# reg-board-1.net
KiCad netlist of a schematic drawn in EAGLE
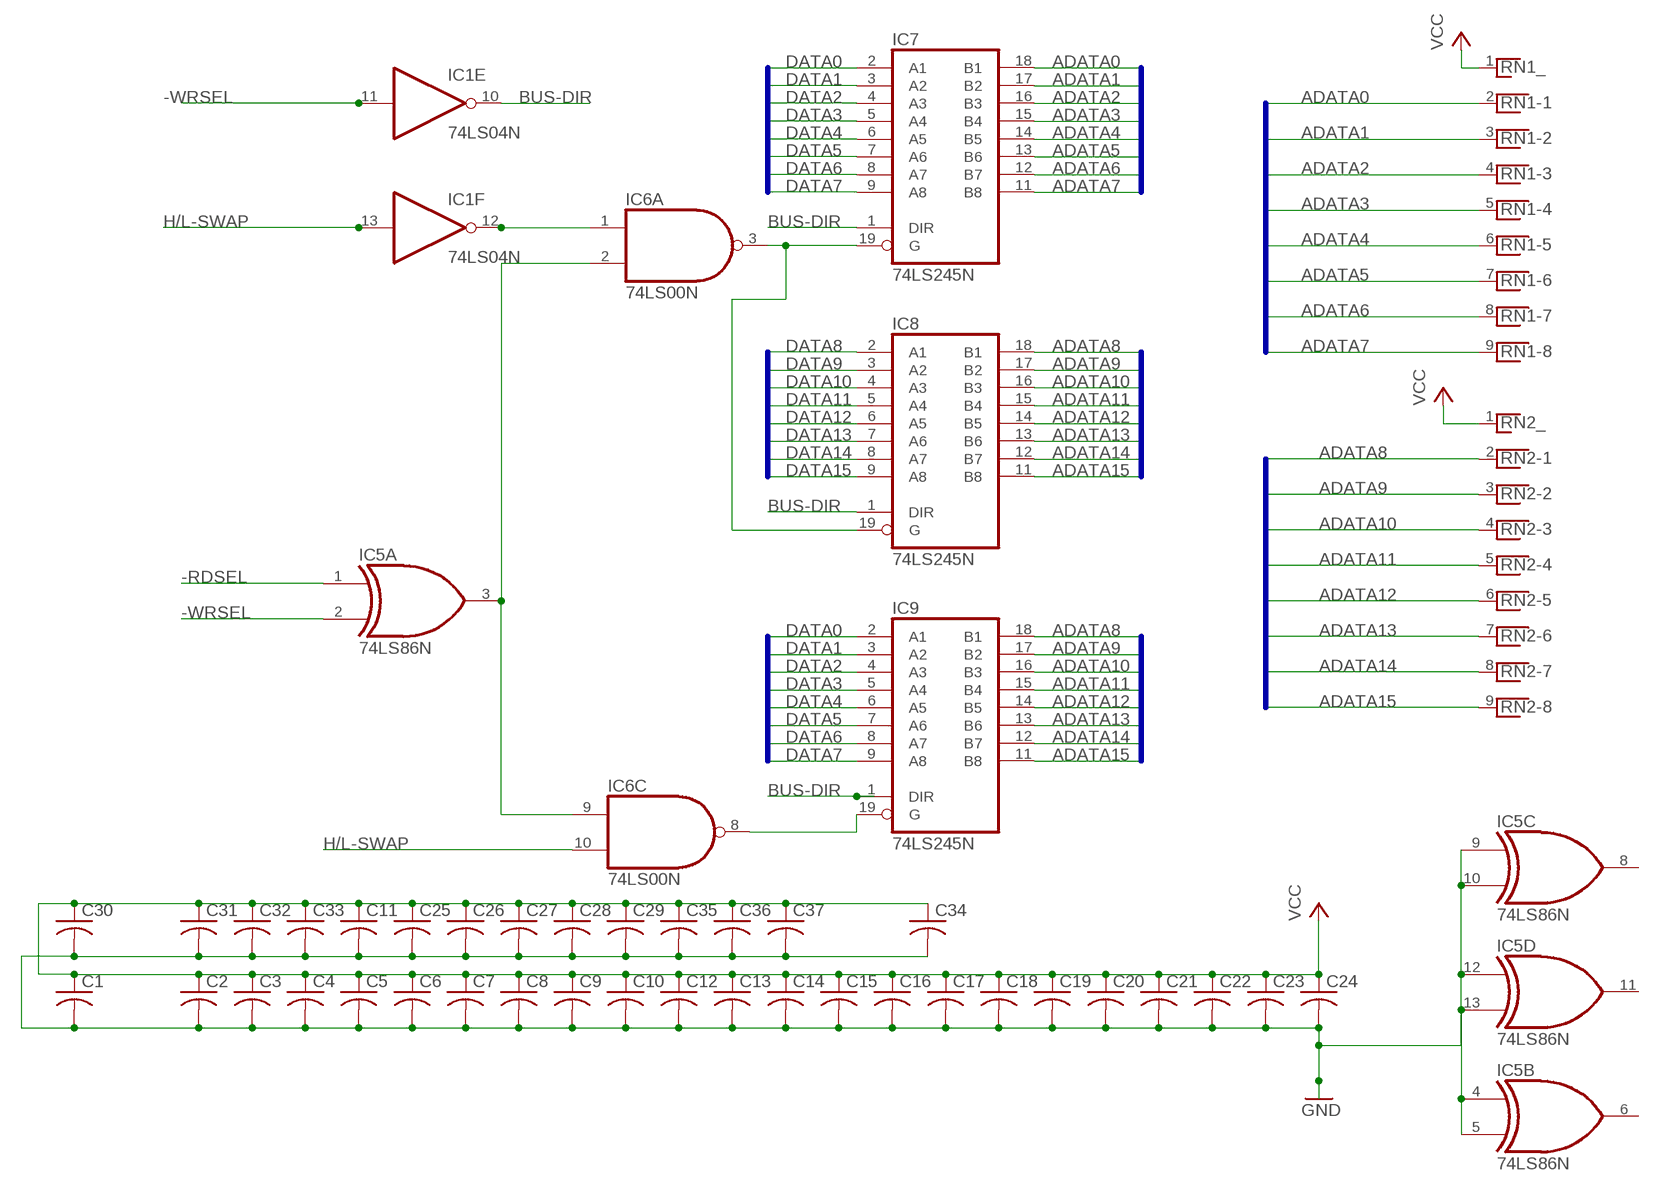
[diagram p0: schematic, sheet 1]
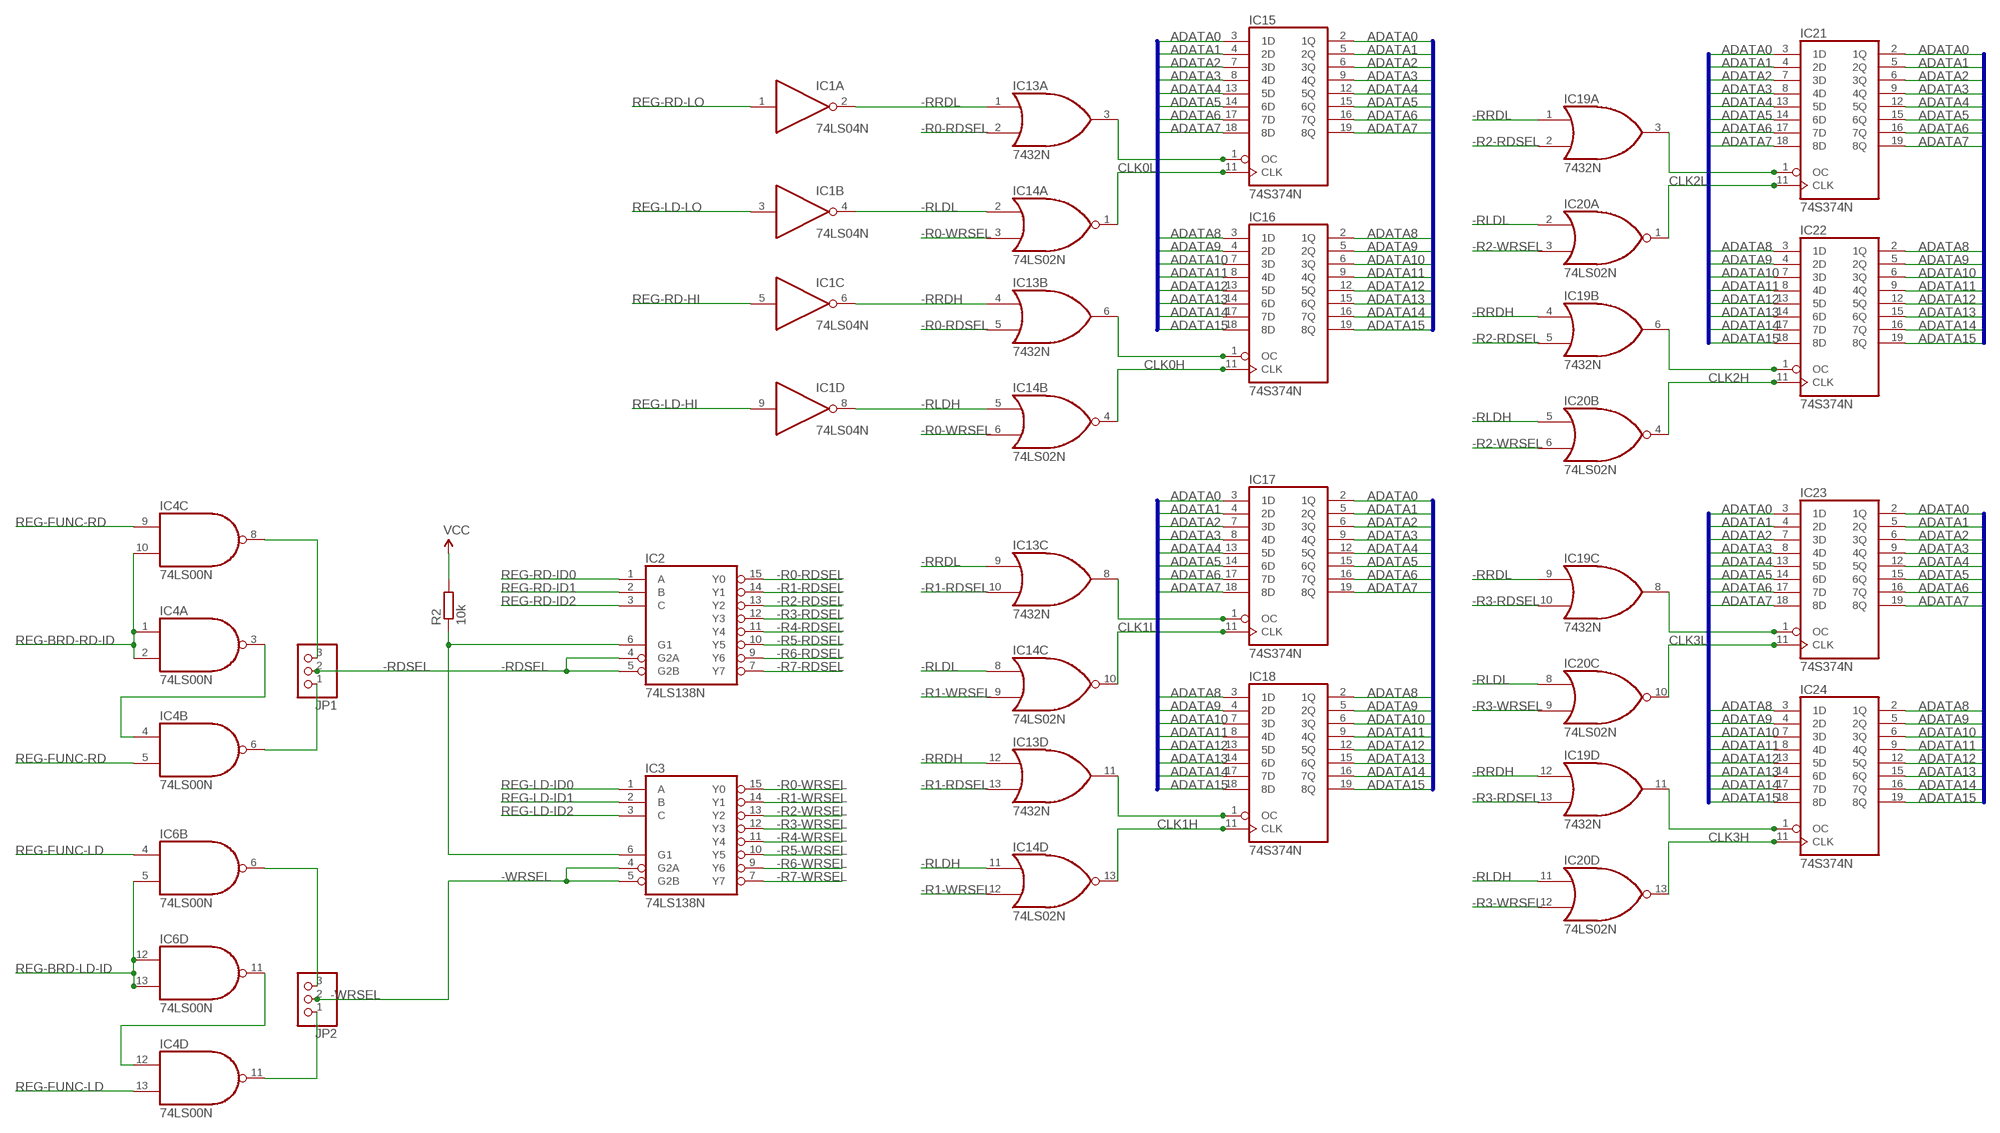
[diagram p1: schematic, sheet 2]
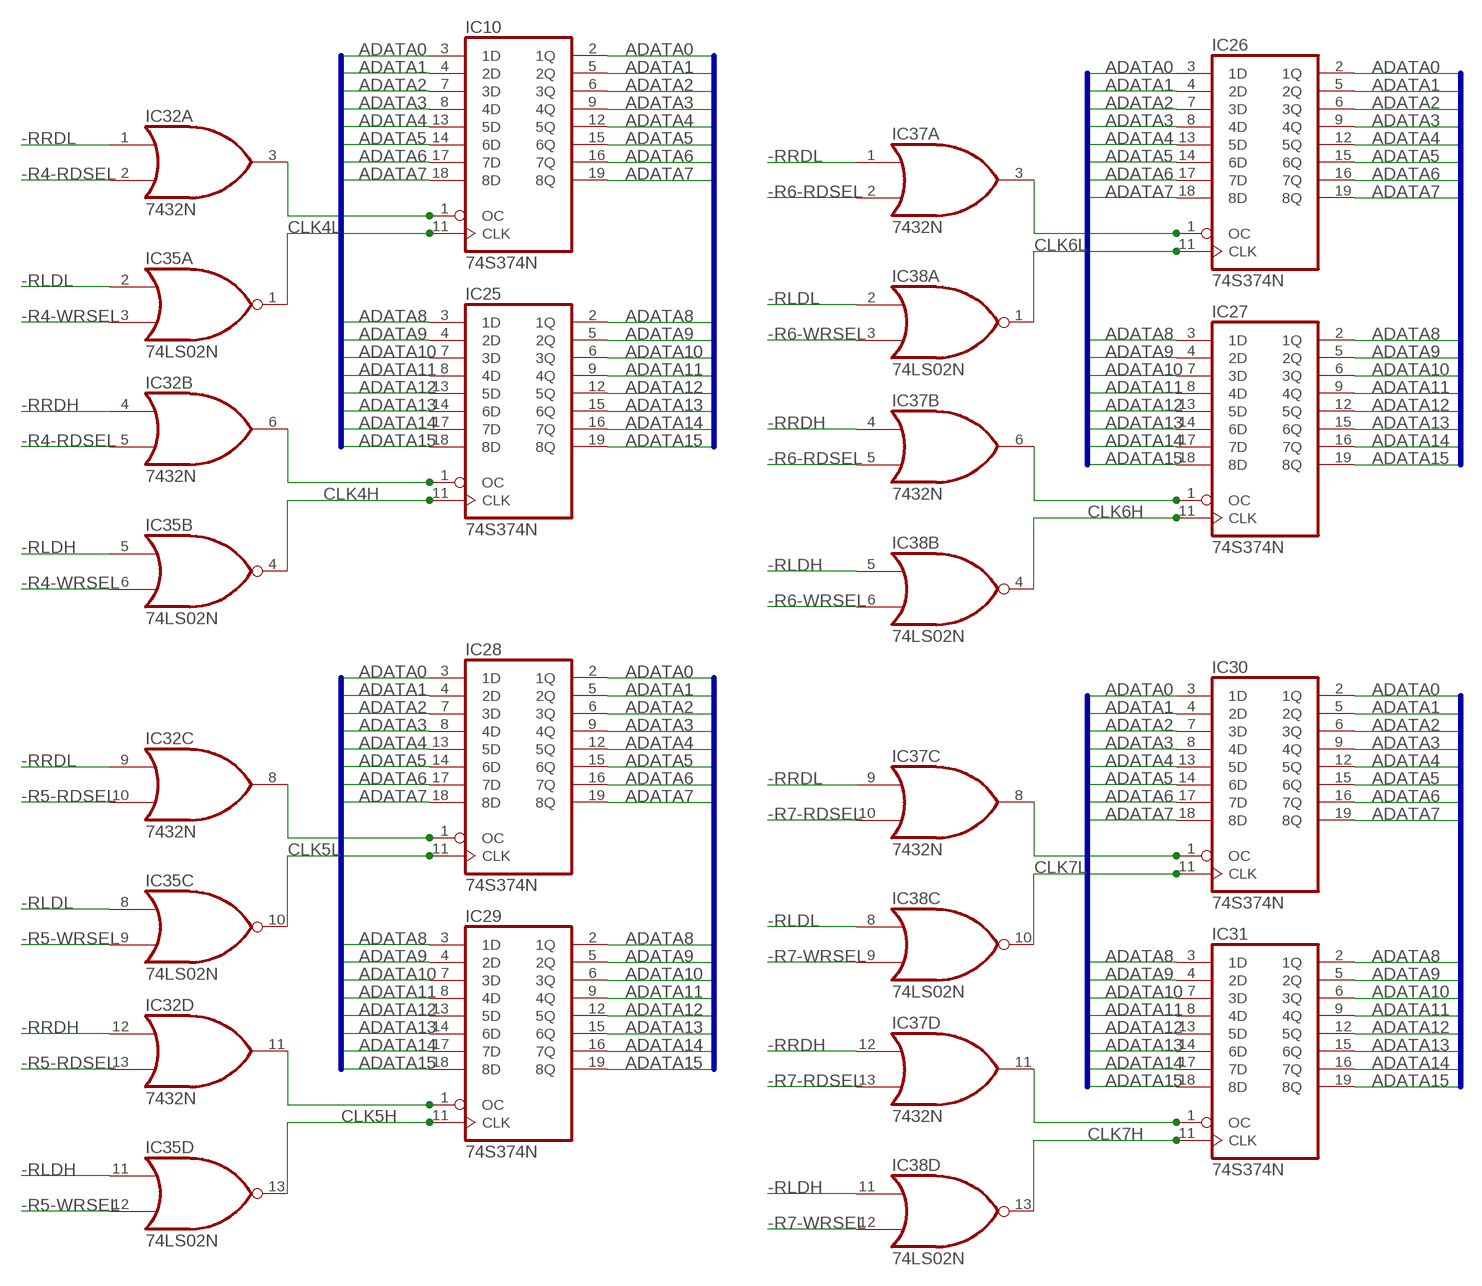
[diagram p2: schematic, sheet 3]
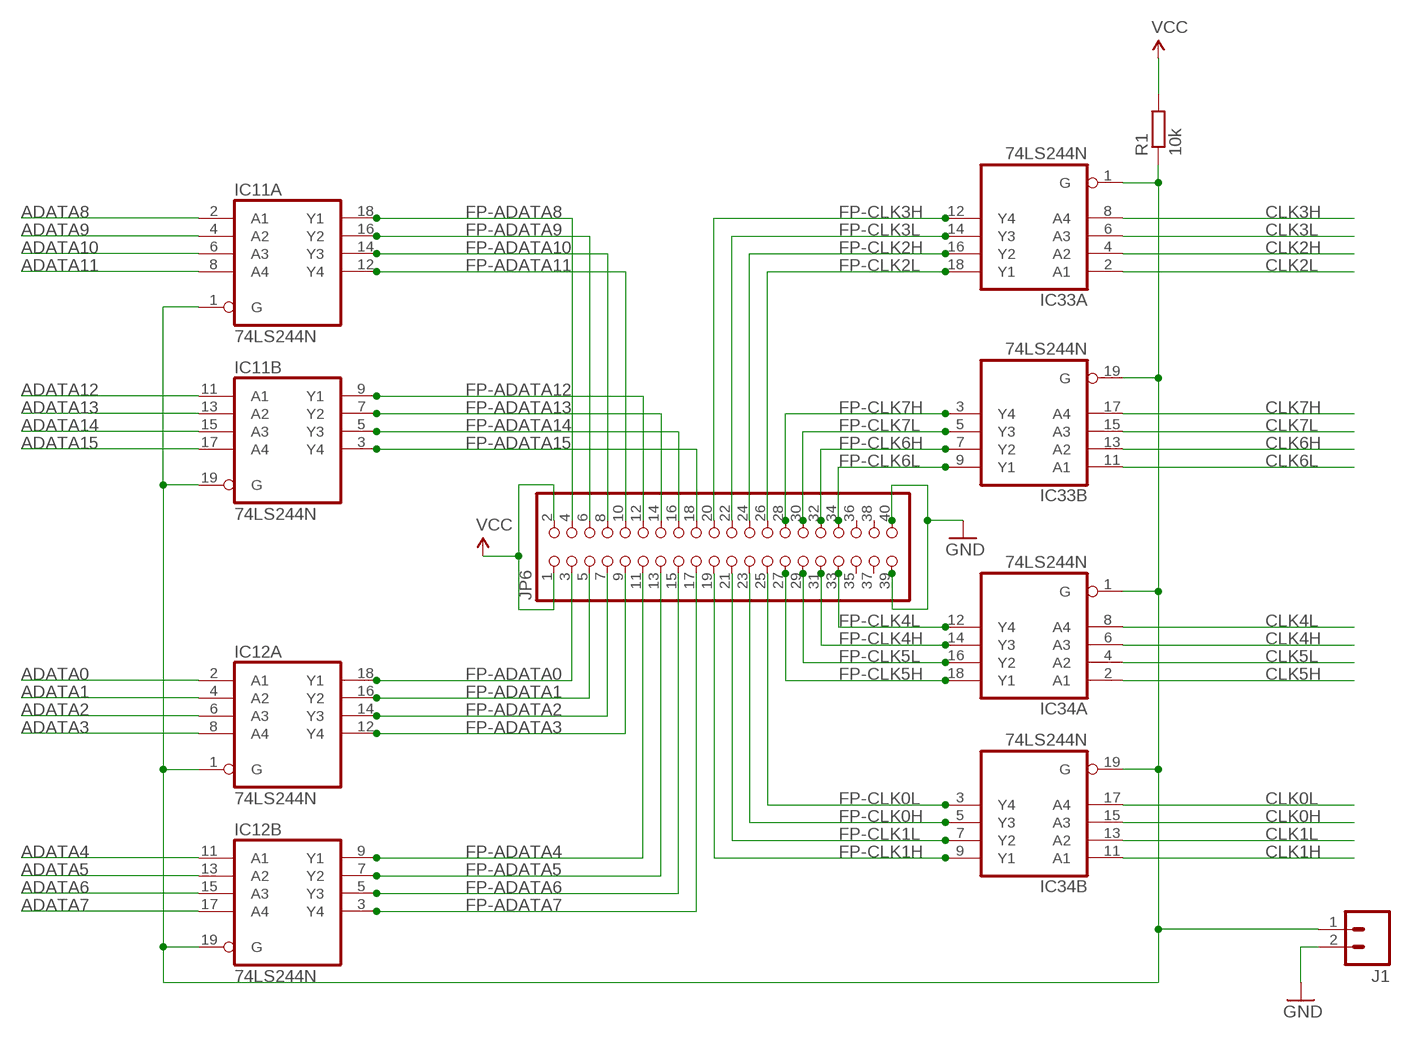
[diagram p3: schematic, sheet 4]
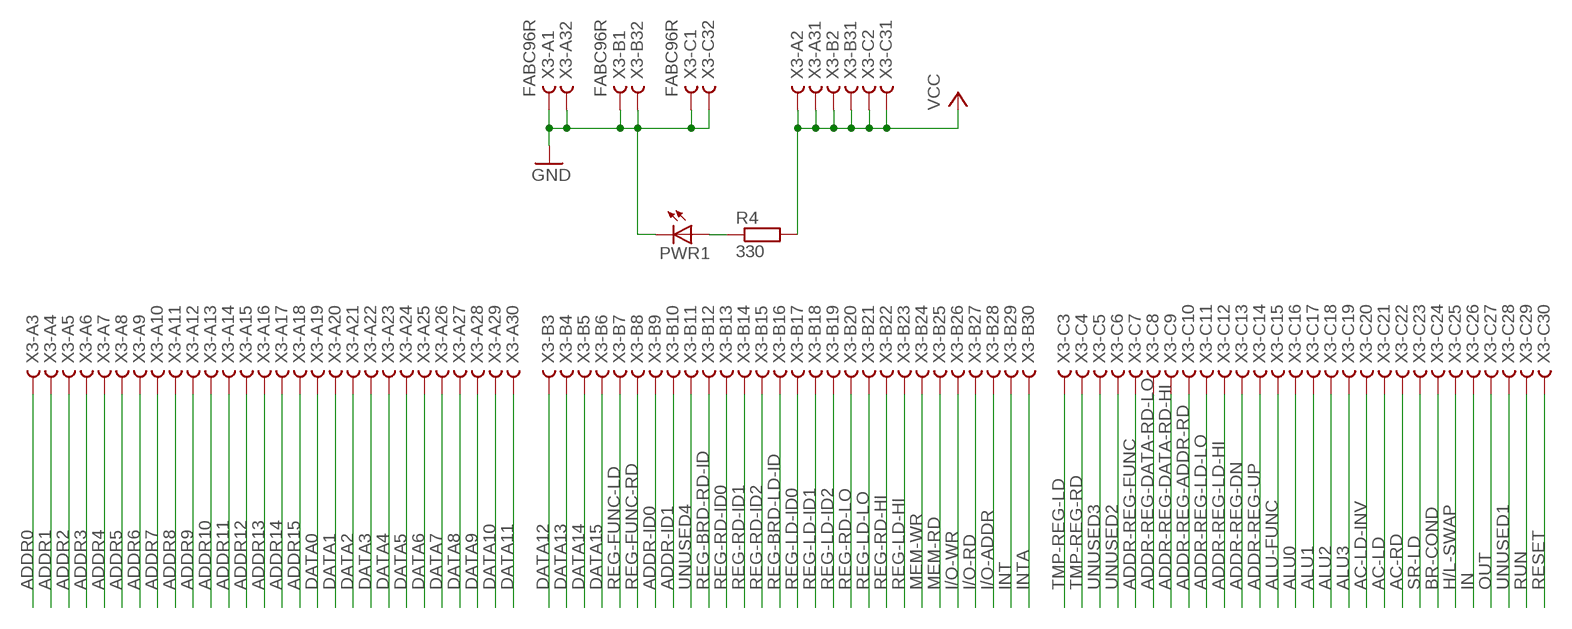
[diagram p4: schematic, sheet 5]

(export (version "E")
  (design (tool "Eeschema 10.0.6"))
  (components
    (comp (ref "IC1")
      (value "74LS04N")
      (footprint "eagle-import:DIL14")
      (libsource (lib "eagle-import") (part "7404NLS"))
    )
    (comp (ref "IC2")
      (value "74LS138N")
      (footprint "eagle-import:DIL16")
      (libsource (lib "eagle-import") (part "74138NLS"))
    )
    (comp (ref "IC3")
      (value "74LS138N")
      (footprint "eagle-import:DIL16")
      (libsource (lib "eagle-import") (part "74138NLS"))
    )
    (comp (ref "IC4")
      (value "74LS00N")
      (footprint "eagle-import:DIL14")
      (libsource (lib "eagle-import") (part "7400NLS"))
    )
    (comp (ref "IC6")
      (value "74LS00N")
      (footprint "eagle-import:DIL14")
      (libsource (lib "eagle-import") (part "7400NLS"))
    )
    (comp (ref "IC13")
      (value "7432N")
      (footprint "eagle-import:DIL14")
      (libsource (lib "eagle-import") (part "7432N"))
    )
    (comp (ref "IC14")
      (value "74LS02N")
      (footprint "eagle-import:DIL14")
      (libsource (lib "eagle-import") (part "7402NLS"))
    )
    (comp (ref "IC15")
      (value "74S374N")
      (footprint "eagle-import:DIL20")
      (libsource (lib "eagle-import") (part "74374NS"))
    )
    (comp (ref "IC16")
      (value "74S374N")
      (footprint "eagle-import:DIL20")
      (libsource (lib "eagle-import") (part "74374NS"))
    )
    (comp (ref "IC17")
      (value "74S374N")
      (footprint "eagle-import:DIL20")
      (libsource (lib "eagle-import") (part "74374NS"))
    )
    (comp (ref "IC18")
      (value "74S374N")
      (footprint "eagle-import:DIL20")
      (libsource (lib "eagle-import") (part "74374NS"))
    )
    (comp (ref "IC19")
      (value "7432N")
      (footprint "eagle-import:DIL14")
      (libsource (lib "eagle-import") (part "7432N"))
    )
    (comp (ref "IC20")
      (value "74LS02N")
      (footprint "eagle-import:DIL14")
      (libsource (lib "eagle-import") (part "7402NLS"))
    )
    (comp (ref "IC21")
      (value "74S374N")
      (footprint "eagle-import:DIL20")
      (libsource (lib "eagle-import") (part "74374NS"))
    )
    (comp (ref "IC22")
      (value "74S374N")
      (footprint "eagle-import:DIL20")
      (libsource (lib "eagle-import") (part "74374NS"))
    )
    (comp (ref "IC23")
      (value "74S374N")
      (footprint "eagle-import:DIL20")
      (libsource (lib "eagle-import") (part "74374NS"))
    )
    (comp (ref "IC24")
      (value "74S374N")
      (footprint "eagle-import:DIL20")
      (libsource (lib "eagle-import") (part "74374NS"))
    )
    (comp (ref "JP1")
      (value "PINHD-1X3")
      (footprint "eagle-import:1X03")
      (libsource (lib "eagle-import") (part "PINHD-1X3"))
    )
    (comp (ref "JP2")
      (value "PINHD-1X3")
      (footprint "eagle-import:1X03")
      (libsource (lib "eagle-import") (part "PINHD-1X3"))
    )
    (comp (ref "R2")
      (value "10k")
      (footprint "eagle-import:0207_10")
      (libsource (lib "eagle-import") (part "R0207/10"))
    )
    (comp (ref "C1")
      (value "C-US025-040X050")
      (footprint "eagle-import:C025-040X050")
      (libsource (lib "eagle-import") (part "C-US025-040X050"))
    )
    (comp (ref "C2")
      (value "C-US025-040X050")
      (footprint "eagle-import:C025-040X050")
      (libsource (lib "eagle-import") (part "C-US025-040X050"))
    )
    (comp (ref "C3")
      (value "C-US025-040X050")
      (footprint "eagle-import:C025-040X050")
      (libsource (lib "eagle-import") (part "C-US025-040X050"))
    )
    (comp (ref "C4")
      (value "C-US025-040X050")
      (footprint "eagle-import:C025-040X050")
      (libsource (lib "eagle-import") (part "C-US025-040X050"))
    )
    (comp (ref "C5")
      (value "C-US025-040X050")
      (footprint "eagle-import:C025-040X050")
      (libsource (lib "eagle-import") (part "C-US025-040X050"))
    )
    (comp (ref "C6")
      (value "C-US025-040X050")
      (footprint "eagle-import:C025-040X050")
      (libsource (lib "eagle-import") (part "C-US025-040X050"))
    )
    (comp (ref "C7")
      (value "C-US025-040X050")
      (footprint "eagle-import:C025-040X050")
      (libsource (lib "eagle-import") (part "C-US025-040X050"))
    )
    (comp (ref "C8")
      (value "C-US025-040X050")
      (footprint "eagle-import:C025-040X050")
      (libsource (lib "eagle-import") (part "C-US025-040X050"))
    )
    (comp (ref "C9")
      (value "C-US025-040X050")
      (footprint "eagle-import:C025-040X050")
      (libsource (lib "eagle-import") (part "C-US025-040X050"))
    )
    (comp (ref "C10")
      (value "C-US025-040X050")
      (footprint "eagle-import:C025-040X050")
      (libsource (lib "eagle-import") (part "C-US025-040X050"))
    )
    (comp (ref "C11")
      (value "C-US025-040X050")
      (footprint "eagle-import:C025-040X050")
      (libsource (lib "eagle-import") (part "C-US025-040X050"))
    )
    (comp (ref "C12")
      (value "C-US025-040X050")
      (footprint "eagle-import:C025-040X050")
      (libsource (lib "eagle-import") (part "C-US025-040X050"))
    )
    (comp (ref "C13")
      (value "C-US025-040X050")
      (footprint "eagle-import:C025-040X050")
      (libsource (lib "eagle-import") (part "C-US025-040X050"))
    )
    (comp (ref "C14")
      (value "C-US025-040X050")
      (footprint "eagle-import:C025-040X050")
      (libsource (lib "eagle-import") (part "C-US025-040X050"))
    )
    (comp (ref "C15")
      (value "C-US025-040X050")
      (footprint "eagle-import:C025-040X050")
      (libsource (lib "eagle-import") (part "C-US025-040X050"))
    )
    (comp (ref "C16")
      (value "C-US025-040X050")
      (footprint "eagle-import:C025-040X050")
      (libsource (lib "eagle-import") (part "C-US025-040X050"))
    )
    (comp (ref "C17")
      (value "C-US025-040X050")
      (footprint "eagle-import:C025-040X050")
      (libsource (lib "eagle-import") (part "C-US025-040X050"))
    )
    (comp (ref "C18")
      (value "C-US025-040X050")
      (footprint "eagle-import:C025-040X050")
      (libsource (lib "eagle-import") (part "C-US025-040X050"))
    )
    (comp (ref "C19")
      (value "C-US025-040X050")
      (footprint "eagle-import:C025-040X050")
      (libsource (lib "eagle-import") (part "C-US025-040X050"))
    )
    (comp (ref "C20")
      (value "C-US025-040X050")
      (footprint "eagle-import:C025-040X050")
      (libsource (lib "eagle-import") (part "C-US025-040X050"))
    )
    (comp (ref "C21")
      (value "C-US025-040X050")
      (footprint "eagle-import:C025-040X050")
      (libsource (lib "eagle-import") (part "C-US025-040X050"))
    )
    (comp (ref "C22")
      (value "C-US025-040X050")
      (footprint "eagle-import:C025-040X050")
      (libsource (lib "eagle-import") (part "C-US025-040X050"))
    )
    (comp (ref "C23")
      (value "C-US025-040X050")
      (footprint "eagle-import:C025-040X050")
      (libsource (lib "eagle-import") (part "C-US025-040X050"))
    )
    (comp (ref "C24")
      (value "C-US025-040X050")
      (footprint "eagle-import:C025-040X050")
      (libsource (lib "eagle-import") (part "C-US025-040X050"))
    )
    (comp (ref "C25")
      (value "C-US025-040X050")
      (footprint "eagle-import:C025-040X050")
      (libsource (lib "eagle-import") (part "C-US025-040X050"))
    )
    (comp (ref "C26")
      (value "C-US025-040X050")
      (footprint "eagle-import:C025-040X050")
      (libsource (lib "eagle-import") (part "C-US025-040X050"))
    )
    (comp (ref "C27")
      (value "C-US025-040X050")
      (footprint "eagle-import:C025-040X050")
      (libsource (lib "eagle-import") (part "C-US025-040X050"))
    )
    (comp (ref "C28")
      (value "C-US025-040X050")
      (footprint "eagle-import:C025-040X050")
      (libsource (lib "eagle-import") (part "C-US025-040X050"))
    )
    (comp (ref "C29")
      (value "C-US025-040X050")
      (footprint "eagle-import:C025-040X050")
      (libsource (lib "eagle-import") (part "C-US025-040X050"))
    )
    (comp (ref "C30")
      (value "C-US025-040X050")
      (footprint "eagle-import:C025-040X050")
      (libsource (lib "eagle-import") (part "C-US025-040X050"))
    )
    (comp (ref "C31")
      (value "C-US025-040X050")
      (footprint "eagle-import:C025-040X050")
      (libsource (lib "eagle-import") (part "C-US025-040X050"))
    )
    (comp (ref "C32")
      (value "C-US025-040X050")
      (footprint "eagle-import:C025-040X050")
      (libsource (lib "eagle-import") (part "C-US025-040X050"))
    )
    (comp (ref "C33")
      (value "C-US025-040X050")
      (footprint "eagle-import:C025-040X050")
      (libsource (lib "eagle-import") (part "C-US025-040X050"))
    )
    (comp (ref "C34")
      (value "C-US025-040X050")
      (footprint "eagle-import:C025-040X050")
      (libsource (lib "eagle-import") (part "C-US025-040X050"))
    )
    (comp (ref "C35")
      (value "C-US025-040X050")
      (footprint "eagle-import:C025-040X050")
      (libsource (lib "eagle-import") (part "C-US025-040X050"))
    )
    (comp (ref "C36")
      (value "C-US025-040X050")
      (footprint "eagle-import:C025-040X050")
      (libsource (lib "eagle-import") (part "C-US025-040X050"))
    )
    (comp (ref "C37")
      (value "C-US025-040X050")
      (footprint "eagle-import:C025-040X050")
      (libsource (lib "eagle-import") (part "C-US025-040X050"))
    )
    (comp (ref "IC5")
      (value "74LS86N")
      (footprint "eagle-import:DIL14")
      (libsource (lib "eagle-import") (part "7486NLS"))
    )
    (comp (ref "IC7")
      (value "74LS245N")
      (footprint "eagle-import:DIL20")
      (libsource (lib "eagle-import") (part "74245NLS"))
    )
    (comp (ref "IC8")
      (value "74LS245N")
      (footprint "eagle-import:DIL20")
      (libsource (lib "eagle-import") (part "74245NLS"))
    )
    (comp (ref "IC9")
      (value "74LS245N")
      (footprint "eagle-import:DIL20")
      (libsource (lib "eagle-import") (part "74245NLS"))
    )
    (comp (ref "RN1")
      (value "RNX8")
      (footprint "eagle-import:RN-9")
      (libsource (lib "eagle-import") (part "RNX8"))
    )
    (comp (ref "RN2")
      (value "RNX8")
      (footprint "eagle-import:RN-9")
      (libsource (lib "eagle-import") (part "RNX8"))
    )
    (comp (ref "IC10")
      (value "74S374N")
      (footprint "eagle-import:DIL20")
      (libsource (lib "eagle-import") (part "74374NS"))
    )
    (comp (ref "IC25")
      (value "74S374N")
      (footprint "eagle-import:DIL20")
      (libsource (lib "eagle-import") (part "74374NS"))
    )
    (comp (ref "IC26")
      (value "74S374N")
      (footprint "eagle-import:DIL20")
      (libsource (lib "eagle-import") (part "74374NS"))
    )
    (comp (ref "IC27")
      (value "74S374N")
      (footprint "eagle-import:DIL20")
      (libsource (lib "eagle-import") (part "74374NS"))
    )
    (comp (ref "IC28")
      (value "74S374N")
      (footprint "eagle-import:DIL20")
      (libsource (lib "eagle-import") (part "74374NS"))
    )
    (comp (ref "IC29")
      (value "74S374N")
      (footprint "eagle-import:DIL20")
      (libsource (lib "eagle-import") (part "74374NS"))
    )
    (comp (ref "IC30")
      (value "74S374N")
      (footprint "eagle-import:DIL20")
      (libsource (lib "eagle-import") (part "74374NS"))
    )
    (comp (ref "IC31")
      (value "74S374N")
      (footprint "eagle-import:DIL20")
      (libsource (lib "eagle-import") (part "74374NS"))
    )
    (comp (ref "IC32")
      (value "7432N")
      (footprint "eagle-import:DIL14")
      (libsource (lib "eagle-import") (part "7432N"))
    )
    (comp (ref "IC35")
      (value "74LS02N")
      (footprint "eagle-import:DIL14")
      (libsource (lib "eagle-import") (part "7402NLS"))
    )
    (comp (ref "IC37")
      (value "7432N")
      (footprint "eagle-import:DIL14")
      (libsource (lib "eagle-import") (part "7432N"))
    )
    (comp (ref "IC38")
      (value "74LS02N")
      (footprint "eagle-import:DIL14")
      (libsource (lib "eagle-import") (part "7402NLS"))
    )
    (comp (ref "IC11")
      (value "74LS244N")
      (footprint "eagle-import:DIL20")
      (libsource (lib "eagle-import") (part "74xx-us_74244NLS"))
    )
    (comp (ref "IC12")
      (value "74LS244N")
      (footprint "eagle-import:DIL20")
      (libsource (lib "eagle-import") (part "74xx-us_74244NLS"))
    )
    (comp (ref "IC33")
      (value "74LS244N")
      (footprint "eagle-import:DIL20")
      (libsource (lib "eagle-import") (part "74xx-us_74244NLS"))
    )
    (comp (ref "IC34")
      (value "74LS244N")
      (footprint "eagle-import:DIL20")
      (libsource (lib "eagle-import") (part "74xx-us_74244NLS"))
    )
    (comp (ref "J1")
      (value "M02PTH")
      (footprint "eagle-import:1X02")
      (libsource (lib "eagle-import") (part "M02PTH"))
    )
    (comp (ref "JP6")
      (value "PINHD-2X20")
      (footprint "eagle-import:2X20")
      (libsource (lib "eagle-import") (part "PINHD-2X20"))
    )
    (comp (ref "R1")
      (value "10k")
      (footprint "eagle-import:0207_10")
      (libsource (lib "eagle-import") (part "R0207/10"))
    )
    (comp (ref "PWR1")
      (value "LED5MM")
      (footprint "eagle-import:LED5MM")
      (libsource (lib "eagle-import") (part "LED5MM"))
    )
    (comp (ref "R4")
      (value "330")
      (footprint "eagle-import:0207_10")
      (libsource (lib "eagle-import") (part "R0207/10"))
    )
    (comp (ref "X3")
      (value "FABC96R")
      (footprint "eagle-import:FABC96R")
      (libsource (lib "eagle-import") (part "FABC96R"))
    )
  )
  (nets
    (net (code "1") (name "-R0-RDSEL") (class "Default")
      (node (ref "IC13") (pin "2") (pinfunction "I1_2") (pintype "input"))
      (node (ref "IC13") (pin "5") (pinfunction "I1_5") (pintype "input"))
      (node (ref "IC2") (pin "15") (pinfunction "Y0_15") (pintype "output"))
    )
    (net (code "2") (name "-R0-WRSEL") (class "Default")
      (node (ref "IC14") (pin "3") (pinfunction "I1_3") (pintype "input"))
      (node (ref "IC14") (pin "6") (pinfunction "I1_6") (pintype "input"))
      (node (ref "IC3") (pin "15") (pinfunction "Y0_15") (pintype "output"))
    )
    (net (code "3") (name "-R1-RDSEL") (class "Default")
      (node (ref "IC13") (pin "10") (pinfunction "I1_10") (pintype "input"))
      (node (ref "IC13") (pin "13") (pinfunction "I1_13") (pintype "input"))
      (node (ref "IC2") (pin "14") (pinfunction "Y1_14") (pintype "output"))
    )
    (net (code "4") (name "-R1-WRSEL") (class "Default")
      (node (ref "IC14") (pin "12") (pinfunction "I1_12") (pintype "input"))
      (node (ref "IC14") (pin "9") (pinfunction "I1_9") (pintype "input"))
      (node (ref "IC3") (pin "14") (pinfunction "Y1_14") (pintype "output"))
    )
    (net (code "5") (name "-R2-RDSEL") (class "Default")
      (node (ref "IC19") (pin "2") (pinfunction "I1_2") (pintype "input"))
      (node (ref "IC19") (pin "5") (pinfunction "I1_5") (pintype "input"))
      (node (ref "IC2") (pin "13") (pinfunction "Y2_13") (pintype "output"))
    )
    (net (code "6") (name "-R2-WRSEL") (class "Default")
      (node (ref "IC20") (pin "3") (pinfunction "I1_3") (pintype "input"))
      (node (ref "IC20") (pin "6") (pinfunction "I1_6") (pintype "input"))
      (node (ref "IC3") (pin "13") (pinfunction "Y2_13") (pintype "output"))
    )
    (net (code "7") (name "-R3-RDSEL") (class "Default")
      (node (ref "IC19") (pin "10") (pinfunction "I1_10") (pintype "input"))
      (node (ref "IC19") (pin "13") (pinfunction "I1_13") (pintype "input"))
      (node (ref "IC2") (pin "12") (pinfunction "Y3_12") (pintype "output"))
    )
    (net (code "8") (name "-R3-WRSEL") (class "Default")
      (node (ref "IC20") (pin "12") (pinfunction "I1_12") (pintype "input"))
      (node (ref "IC20") (pin "9") (pinfunction "I1_9") (pintype "input"))
      (node (ref "IC3") (pin "12") (pinfunction "Y3_12") (pintype "output"))
    )
    (net (code "9") (name "-R4-RDSEL") (class "Default")
      (node (ref "IC2") (pin "11") (pinfunction "Y4_11") (pintype "output"))
      (node (ref "IC32") (pin "2") (pinfunction "I1_2") (pintype "input"))
      (node (ref "IC32") (pin "5") (pinfunction "I1_5") (pintype "input"))
    )
    (net (code "10") (name "-R4-WRSEL") (class "Default")
      (node (ref "IC3") (pin "11") (pinfunction "Y4_11") (pintype "output"))
      (node (ref "IC35") (pin "3") (pinfunction "I1_3") (pintype "input"))
      (node (ref "IC35") (pin "6") (pinfunction "I1_6") (pintype "input"))
    )
    (net (code "11") (name "-R5-RDSEL") (class "Default")
      (node (ref "IC2") (pin "10") (pinfunction "Y5_10") (pintype "output"))
      (node (ref "IC32") (pin "10") (pinfunction "I1_10") (pintype "input"))
      (node (ref "IC32") (pin "13") (pinfunction "I1_13") (pintype "input"))
    )
    (net (code "12") (name "-R5-WRSEL") (class "Default")
      (node (ref "IC3") (pin "10") (pinfunction "Y5_10") (pintype "output"))
      (node (ref "IC35") (pin "12") (pinfunction "I1_12") (pintype "input"))
      (node (ref "IC35") (pin "9") (pinfunction "I1_9") (pintype "input"))
    )
    (net (code "13") (name "-R6-RDSEL") (class "Default")
      (node (ref "IC2") (pin "9") (pinfunction "Y6_9") (pintype "output"))
      (node (ref "IC37") (pin "2") (pinfunction "I1_2") (pintype "input"))
      (node (ref "IC37") (pin "5") (pinfunction "I1_5") (pintype "input"))
    )
    (net (code "14") (name "-R6-WRSEL") (class "Default")
      (node (ref "IC3") (pin "9") (pinfunction "Y6_9") (pintype "output"))
      (node (ref "IC38") (pin "3") (pinfunction "I1_3") (pintype "input"))
      (node (ref "IC38") (pin "6") (pinfunction "I1_6") (pintype "input"))
    )
    (net (code "15") (name "-R7-RDSEL") (class "Default")
      (node (ref "IC2") (pin "7") (pinfunction "Y7_7") (pintype "output"))
      (node (ref "IC37") (pin "10") (pinfunction "I1_10") (pintype "input"))
      (node (ref "IC37") (pin "13") (pinfunction "I1_13") (pintype "input"))
    )
    (net (code "16") (name "-R7-WRSEL") (class "Default")
      (node (ref "IC3") (pin "7") (pinfunction "Y7_7") (pintype "output"))
      (node (ref "IC38") (pin "12") (pinfunction "I1_12") (pintype "input"))
      (node (ref "IC38") (pin "9") (pinfunction "I1_9") (pintype "input"))
    )
    (net (code "17") (name "-RDSEL") (class "Default")
      (node (ref "IC2") (pin "4") (pinfunction "G2A_4") (pintype "input"))
      (node (ref "IC2") (pin "5") (pinfunction "G2B_5") (pintype "input"))
      (node (ref "IC5") (pin "1") (pinfunction "I0_1") (pintype "input"))
      (node (ref "JP1") (pin "2") (pinfunction "2_2") (pintype "passive"))
    )
    (net (code "18") (name "-RLDH") (class "Default")
      (node (ref "IC1") (pin "8") (pinfunction "O_8") (pintype "output"))
      (node (ref "IC14") (pin "11") (pinfunction "I0_11") (pintype "input"))
      (node (ref "IC14") (pin "5") (pinfunction "I0_5") (pintype "input"))
      (node (ref "IC20") (pin "11") (pinfunction "I0_11") (pintype "input"))
      (node (ref "IC20") (pin "5") (pinfunction "I0_5") (pintype "input"))
      (node (ref "IC35") (pin "11") (pinfunction "I0_11") (pintype "input"))
      (node (ref "IC35") (pin "5") (pinfunction "I0_5") (pintype "input"))
      (node (ref "IC38") (pin "11") (pinfunction "I0_11") (pintype "input"))
      (node (ref "IC38") (pin "5") (pinfunction "I0_5") (pintype "input"))
    )
    (net (code "19") (name "-RLDL") (class "Default")
      (node (ref "IC1") (pin "4") (pinfunction "O_4") (pintype "output"))
      (node (ref "IC14") (pin "2") (pinfunction "I0_2") (pintype "input"))
      (node (ref "IC14") (pin "8") (pinfunction "I0_8") (pintype "input"))
      (node (ref "IC20") (pin "2") (pinfunction "I0_2") (pintype "input"))
      (node (ref "IC20") (pin "8") (pinfunction "I0_8") (pintype "input"))
      (node (ref "IC35") (pin "2") (pinfunction "I0_2") (pintype "input"))
      (node (ref "IC35") (pin "8") (pinfunction "I0_8") (pintype "input"))
      (node (ref "IC38") (pin "2") (pinfunction "I0_2") (pintype "input"))
      (node (ref "IC38") (pin "8") (pinfunction "I0_8") (pintype "input"))
    )
    (net (code "20") (name "-RRDH") (class "Default")
      (node (ref "IC1") (pin "6") (pinfunction "O_6") (pintype "output"))
      (node (ref "IC13") (pin "12") (pinfunction "I0_12") (pintype "input"))
      (node (ref "IC13") (pin "4") (pinfunction "I0_4") (pintype "input"))
      (node (ref "IC19") (pin "12") (pinfunction "I0_12") (pintype "input"))
      (node (ref "IC19") (pin "4") (pinfunction "I0_4") (pintype "input"))
      (node (ref "IC32") (pin "12") (pinfunction "I0_12") (pintype "input"))
      (node (ref "IC32") (pin "4") (pinfunction "I0_4") (pintype "input"))
      (node (ref "IC37") (pin "12") (pinfunction "I0_12") (pintype "input"))
      (node (ref "IC37") (pin "4") (pinfunction "I0_4") (pintype "input"))
    )
    (net (code "21") (name "-RRDL") (class "Default")
      (node (ref "IC1") (pin "2") (pinfunction "O_2") (pintype "output"))
      (node (ref "IC13") (pin "1") (pinfunction "I0_1") (pintype "input"))
      (node (ref "IC13") (pin "9") (pinfunction "I0_9") (pintype "input"))
      (node (ref "IC19") (pin "1") (pinfunction "I0_1") (pintype "input"))
      (node (ref "IC19") (pin "9") (pinfunction "I0_9") (pintype "input"))
      (node (ref "IC32") (pin "1") (pinfunction "I0_1") (pintype "input"))
      (node (ref "IC32") (pin "9") (pinfunction "I0_9") (pintype "input"))
      (node (ref "IC37") (pin "1") (pinfunction "I0_1") (pintype "input"))
      (node (ref "IC37") (pin "9") (pinfunction "I0_9") (pintype "input"))
    )
    (net (code "22") (name "-WRSEL") (class "Default")
      (node (ref "IC1") (pin "11") (pinfunction "I_11") (pintype "input"))
      (node (ref "IC3") (pin "4") (pinfunction "G2A_4") (pintype "input"))
      (node (ref "IC3") (pin "5") (pinfunction "G2B_5") (pintype "input"))
      (node (ref "IC5") (pin "2") (pinfunction "I1_2") (pintype "input"))
      (node (ref "JP2") (pin "2") (pinfunction "2_2") (pintype "passive"))
    )
    (net (code "23") (name "AC-LD") (class "Default")
      (node (ref "X3") (pin "C21") (pinfunction "B_C21") (pintype "passive"))
    )
    (net (code "24") (name "AC-LD-INV") (class "Default")
      (node (ref "X3") (pin "C20") (pinfunction "B_C20") (pintype "passive"))
    )
    (net (code "25") (name "AC-RD") (class "Default")
      (node (ref "X3") (pin "C22") (pinfunction "B_C22") (pintype "passive"))
    )
    (net (code "26") (name "ADATA0") (class "Default")
      (node (ref "IC10") (pin "2") (pinfunction "1Q_2") (pintype "tri_state"))
      (node (ref "IC10") (pin "3") (pinfunction "1D_3") (pintype "input"))
      (node (ref "IC12") (pin "2") (pinfunction "A1_2") (pintype "input"))
      (node (ref "IC15") (pin "2") (pinfunction "1Q_2") (pintype "tri_state"))
      (node (ref "IC15") (pin "3") (pinfunction "1D_3") (pintype "input"))
      (node (ref "IC17") (pin "2") (pinfunction "1Q_2") (pintype "tri_state"))
      (node (ref "IC17") (pin "3") (pinfunction "1D_3") (pintype "input"))
      (node (ref "IC21") (pin "2") (pinfunction "1Q_2") (pintype "tri_state"))
      (node (ref "IC21") (pin "3") (pinfunction "1D_3") (pintype "input"))
      (node (ref "IC23") (pin "2") (pinfunction "1Q_2") (pintype "tri_state"))
      (node (ref "IC23") (pin "3") (pinfunction "1D_3") (pintype "input"))
      (node (ref "IC26") (pin "2") (pinfunction "1Q_2") (pintype "tri_state"))
      (node (ref "IC26") (pin "3") (pinfunction "1D_3") (pintype "input"))
      (node (ref "IC28") (pin "2") (pinfunction "1Q_2") (pintype "tri_state"))
      (node (ref "IC28") (pin "3") (pinfunction "1D_3") (pintype "input"))
      (node (ref "IC30") (pin "2") (pinfunction "1Q_2") (pintype "tri_state"))
      (node (ref "IC30") (pin "3") (pinfunction "1D_3") (pintype "input"))
      (node (ref "IC7") (pin "18") (pinfunction "B1_18") (pintype "bidirectional"))
      (node (ref "RN1") (pin "2") (pinfunction "1_2") (pintype "passive"))
    )
    (net (code "27") (name "ADATA1") (class "Default")
      (node (ref "IC10") (pin "4") (pinfunction "2D_4") (pintype "input"))
      (node (ref "IC10") (pin "5") (pinfunction "2Q_5") (pintype "tri_state"))
      (node (ref "IC12") (pin "4") (pinfunction "A2_4") (pintype "input"))
      (node (ref "IC15") (pin "4") (pinfunction "2D_4") (pintype "input"))
      (node (ref "IC15") (pin "5") (pinfunction "2Q_5") (pintype "tri_state"))
      (node (ref "IC17") (pin "4") (pinfunction "2D_4") (pintype "input"))
      (node (ref "IC17") (pin "5") (pinfunction "2Q_5") (pintype "tri_state"))
      (node (ref "IC21") (pin "4") (pinfunction "2D_4") (pintype "input"))
      (node (ref "IC21") (pin "5") (pinfunction "2Q_5") (pintype "tri_state"))
      (node (ref "IC23") (pin "4") (pinfunction "2D_4") (pintype "input"))
      (node (ref "IC23") (pin "5") (pinfunction "2Q_5") (pintype "tri_state"))
      (node (ref "IC26") (pin "4") (pinfunction "2D_4") (pintype "input"))
      (node (ref "IC26") (pin "5") (pinfunction "2Q_5") (pintype "tri_state"))
      (node (ref "IC28") (pin "4") (pinfunction "2D_4") (pintype "input"))
      (node (ref "IC28") (pin "5") (pinfunction "2Q_5") (pintype "tri_state"))
      (node (ref "IC30") (pin "4") (pinfunction "2D_4") (pintype "input"))
      (node (ref "IC30") (pin "5") (pinfunction "2Q_5") (pintype "tri_state"))
      (node (ref "IC7") (pin "17") (pinfunction "B2_17") (pintype "bidirectional"))
      (node (ref "RN1") (pin "3") (pinfunction "1_3") (pintype "passive"))
    )
    (net (code "28") (name "ADATA2") (class "Default")
      (node (ref "IC10") (pin "6") (pinfunction "3Q_6") (pintype "tri_state"))
      (node (ref "IC10") (pin "7") (pinfunction "3D_7") (pintype "input"))
      (node (ref "IC12") (pin "6") (pinfunction "A3_6") (pintype "input"))
      (node (ref "IC15") (pin "6") (pinfunction "3Q_6") (pintype "tri_state"))
      (node (ref "IC15") (pin "7") (pinfunction "3D_7") (pintype "input"))
      (node (ref "IC17") (pin "6") (pinfunction "3Q_6") (pintype "tri_state"))
      (node (ref "IC17") (pin "7") (pinfunction "3D_7") (pintype "input"))
      (node (ref "IC21") (pin "6") (pinfunction "3Q_6") (pintype "tri_state"))
      (node (ref "IC21") (pin "7") (pinfunction "3D_7") (pintype "input"))
      (node (ref "IC23") (pin "6") (pinfunction "3Q_6") (pintype "tri_state"))
      (node (ref "IC23") (pin "7") (pinfunction "3D_7") (pintype "input"))
      (node (ref "IC26") (pin "6") (pinfunction "3Q_6") (pintype "tri_state"))
      (node (ref "IC26") (pin "7") (pinfunction "3D_7") (pintype "input"))
      (node (ref "IC28") (pin "6") (pinfunction "3Q_6") (pintype "tri_state"))
      (node (ref "IC28") (pin "7") (pinfunction "3D_7") (pintype "input"))
      (node (ref "IC30") (pin "6") (pinfunction "3Q_6") (pintype "tri_state"))
      (node (ref "IC30") (pin "7") (pinfunction "3D_7") (pintype "input"))
      (node (ref "IC7") (pin "16") (pinfunction "B3_16") (pintype "bidirectional"))
      (node (ref "RN1") (pin "4") (pinfunction "1_4") (pintype "passive"))
    )
    (net (code "29") (name "ADATA3") (class "Default")
      (node (ref "IC10") (pin "8") (pinfunction "4D_8") (pintype "input"))
      (node (ref "IC10") (pin "9") (pinfunction "4Q_9") (pintype "tri_state"))
      (node (ref "IC12") (pin "8") (pinfunction "A4_8") (pintype "input"))
      (node (ref "IC15") (pin "8") (pinfunction "4D_8") (pintype "input"))
      (node (ref "IC15") (pin "9") (pinfunction "4Q_9") (pintype "tri_state"))
      (node (ref "IC17") (pin "8") (pinfunction "4D_8") (pintype "input"))
      (node (ref "IC17") (pin "9") (pinfunction "4Q_9") (pintype "tri_state"))
      (node (ref "IC21") (pin "8") (pinfunction "4D_8") (pintype "input"))
      (node (ref "IC21") (pin "9") (pinfunction "4Q_9") (pintype "tri_state"))
      (node (ref "IC23") (pin "8") (pinfunction "4D_8") (pintype "input"))
      (node (ref "IC23") (pin "9") (pinfunction "4Q_9") (pintype "tri_state"))
      (node (ref "IC26") (pin "8") (pinfunction "4D_8") (pintype "input"))
      (node (ref "IC26") (pin "9") (pinfunction "4Q_9") (pintype "tri_state"))
      (node (ref "IC28") (pin "8") (pinfunction "4D_8") (pintype "input"))
      (node (ref "IC28") (pin "9") (pinfunction "4Q_9") (pintype "tri_state"))
      (node (ref "IC30") (pin "8") (pinfunction "4D_8") (pintype "input"))
      (node (ref "IC30") (pin "9") (pinfunction "4Q_9") (pintype "tri_state"))
      (node (ref "IC7") (pin "15") (pinfunction "B4_15") (pintype "bidirectional"))
      (node (ref "RN1") (pin "5") (pinfunction "1_5") (pintype "passive"))
    )
    (net (code "30") (name "ADATA4") (class "Default")
      (node (ref "IC10") (pin "12") (pinfunction "5Q_12") (pintype "tri_state"))
      (node (ref "IC10") (pin "13") (pinfunction "5D_13") (pintype "input"))
      (node (ref "IC12") (pin "11") (pinfunction "A1_11") (pintype "input"))
      (node (ref "IC15") (pin "12") (pinfunction "5Q_12") (pintype "tri_state"))
      (node (ref "IC15") (pin "13") (pinfunction "5D_13") (pintype "input"))
      (node (ref "IC17") (pin "12") (pinfunction "5Q_12") (pintype "tri_state"))
      (node (ref "IC17") (pin "13") (pinfunction "5D_13") (pintype "input"))
      (node (ref "IC21") (pin "12") (pinfunction "5Q_12") (pintype "tri_state"))
      (node (ref "IC21") (pin "13") (pinfunction "5D_13") (pintype "input"))
      (node (ref "IC23") (pin "12") (pinfunction "5Q_12") (pintype "tri_state"))
      (node (ref "IC23") (pin "13") (pinfunction "5D_13") (pintype "input"))
      (node (ref "IC26") (pin "12") (pinfunction "5Q_12") (pintype "tri_state"))
      (node (ref "IC26") (pin "13") (pinfunction "5D_13") (pintype "input"))
      (node (ref "IC28") (pin "12") (pinfunction "5Q_12") (pintype "tri_state"))
      (node (ref "IC28") (pin "13") (pinfunction "5D_13") (pintype "input"))
      (node (ref "IC30") (pin "12") (pinfunction "5Q_12") (pintype "tri_state"))
      (node (ref "IC30") (pin "13") (pinfunction "5D_13") (pintype "input"))
      (node (ref "IC7") (pin "14") (pinfunction "B5_14") (pintype "bidirectional"))
      (node (ref "RN1") (pin "6") (pinfunction "1_6") (pintype "passive"))
    )
    (net (code "31") (name "ADATA5") (class "Default")
      (node (ref "IC10") (pin "14") (pinfunction "6D_14") (pintype "input"))
      (node (ref "IC10") (pin "15") (pinfunction "6Q_15") (pintype "tri_state"))
      (node (ref "IC12") (pin "13") (pinfunction "A2_13") (pintype "input"))
      (node (ref "IC15") (pin "14") (pinfunction "6D_14") (pintype "input"))
      (node (ref "IC15") (pin "15") (pinfunction "6Q_15") (pintype "tri_state"))
      (node (ref "IC17") (pin "14") (pinfunction "6D_14") (pintype "input"))
      (node (ref "IC17") (pin "15") (pinfunction "6Q_15") (pintype "tri_state"))
      (node (ref "IC21") (pin "14") (pinfunction "6D_14") (pintype "input"))
      (node (ref "IC21") (pin "15") (pinfunction "6Q_15") (pintype "tri_state"))
      (node (ref "IC23") (pin "14") (pinfunction "6D_14") (pintype "input"))
      (node (ref "IC23") (pin "15") (pinfunction "6Q_15") (pintype "tri_state"))
      (node (ref "IC26") (pin "14") (pinfunction "6D_14") (pintype "input"))
      (node (ref "IC26") (pin "15") (pinfunction "6Q_15") (pintype "tri_state"))
      (node (ref "IC28") (pin "14") (pinfunction "6D_14") (pintype "input"))
      (node (ref "IC28") (pin "15") (pinfunction "6Q_15") (pintype "tri_state"))
      (node (ref "IC30") (pin "14") (pinfunction "6D_14") (pintype "input"))
      (node (ref "IC30") (pin "15") (pinfunction "6Q_15") (pintype "tri_state"))
      (node (ref "IC7") (pin "13") (pinfunction "B6_13") (pintype "bidirectional"))
      (node (ref "RN1") (pin "7") (pinfunction "1_7") (pintype "passive"))
    )
    (net (code "32") (name "ADATA6") (class "Default")
      (node (ref "IC10") (pin "16") (pinfunction "7Q_16") (pintype "tri_state"))
      (node (ref "IC10") (pin "17") (pinfunction "7D_17") (pintype "input"))
      (node (ref "IC12") (pin "15") (pinfunction "A3_15") (pintype "input"))
      (node (ref "IC15") (pin "16") (pinfunction "7Q_16") (pintype "tri_state"))
      (node (ref "IC15") (pin "17") (pinfunction "7D_17") (pintype "input"))
      (node (ref "IC17") (pin "16") (pinfunction "7Q_16") (pintype "tri_state"))
      (node (ref "IC17") (pin "17") (pinfunction "7D_17") (pintype "input"))
      (node (ref "IC21") (pin "16") (pinfunction "7Q_16") (pintype "tri_state"))
      (node (ref "IC21") (pin "17") (pinfunction "7D_17") (pintype "input"))
      (node (ref "IC23") (pin "16") (pinfunction "7Q_16") (pintype "tri_state"))
      (node (ref "IC23") (pin "17") (pinfunction "7D_17") (pintype "input"))
      (node (ref "IC26") (pin "16") (pinfunction "7Q_16") (pintype "tri_state"))
      (node (ref "IC26") (pin "17") (pinfunction "7D_17") (pintype "input"))
      (node (ref "IC28") (pin "16") (pinfunction "7Q_16") (pintype "tri_state"))
      (node (ref "IC28") (pin "17") (pinfunction "7D_17") (pintype "input"))
      (node (ref "IC30") (pin "16") (pinfunction "7Q_16") (pintype "tri_state"))
      (node (ref "IC30") (pin "17") (pinfunction "7D_17") (pintype "input"))
      (node (ref "IC7") (pin "12") (pinfunction "B7_12") (pintype "bidirectional"))
      (node (ref "RN1") (pin "8") (pinfunction "1_8") (pintype "passive"))
    )
    (net (code "33") (name "ADATA7") (class "Default")
      (node (ref "IC10") (pin "18") (pinfunction "8D_18") (pintype "input"))
      (node (ref "IC10") (pin "19") (pinfunction "8Q_19") (pintype "tri_state"))
      (node (ref "IC12") (pin "17") (pinfunction "A4_17") (pintype "input"))
      (node (ref "IC15") (pin "18") (pinfunction "8D_18") (pintype "input"))
      (node (ref "IC15") (pin "19") (pinfunction "8Q_19") (pintype "tri_state"))
      (node (ref "IC17") (pin "18") (pinfunction "8D_18") (pintype "input"))
      (node (ref "IC17") (pin "19") (pinfunction "8Q_19") (pintype "tri_state"))
      (node (ref "IC21") (pin "18") (pinfunction "8D_18") (pintype "input"))
      (node (ref "IC21") (pin "19") (pinfunction "8Q_19") (pintype "tri_state"))
      (node (ref "IC23") (pin "18") (pinfunction "8D_18") (pintype "input"))
      (node (ref "IC23") (pin "19") (pinfunction "8Q_19") (pintype "tri_state"))
      (node (ref "IC26") (pin "18") (pinfunction "8D_18") (pintype "input"))
      (node (ref "IC26") (pin "19") (pinfunction "8Q_19") (pintype "tri_state"))
      (node (ref "IC28") (pin "18") (pinfunction "8D_18") (pintype "input"))
      (node (ref "IC28") (pin "19") (pinfunction "8Q_19") (pintype "tri_state"))
      (node (ref "IC30") (pin "18") (pinfunction "8D_18") (pintype "input"))
      (node (ref "IC30") (pin "19") (pinfunction "8Q_19") (pintype "tri_state"))
      (node (ref "IC7") (pin "11") (pinfunction "B8_11") (pintype "bidirectional"))
      (node (ref "RN1") (pin "9") (pinfunction "1_9") (pintype "passive"))
    )
    (net (code "34") (name "ADATA8") (class "Default")
      (node (ref "IC11") (pin "2") (pinfunction "A1_2") (pintype "input"))
      (node (ref "IC16") (pin "2") (pinfunction "1Q_2") (pintype "tri_state"))
      (node (ref "IC16") (pin "3") (pinfunction "1D_3") (pintype "input"))
      (node (ref "IC18") (pin "2") (pinfunction "1Q_2") (pintype "tri_state"))
      (node (ref "IC18") (pin "3") (pinfunction "1D_3") (pintype "input"))
      (node (ref "IC22") (pin "2") (pinfunction "1Q_2") (pintype "tri_state"))
      (node (ref "IC22") (pin "3") (pinfunction "1D_3") (pintype "input"))
      (node (ref "IC24") (pin "2") (pinfunction "1Q_2") (pintype "tri_state"))
      (node (ref "IC24") (pin "3") (pinfunction "1D_3") (pintype "input"))
      (node (ref "IC25") (pin "2") (pinfunction "1Q_2") (pintype "tri_state"))
      (node (ref "IC25") (pin "3") (pinfunction "1D_3") (pintype "input"))
      (node (ref "IC27") (pin "2") (pinfunction "1Q_2") (pintype "tri_state"))
      (node (ref "IC27") (pin "3") (pinfunction "1D_3") (pintype "input"))
      (node (ref "IC29") (pin "2") (pinfunction "1Q_2") (pintype "tri_state"))
      (node (ref "IC29") (pin "3") (pinfunction "1D_3") (pintype "input"))
      (node (ref "IC31") (pin "2") (pinfunction "1Q_2") (pintype "tri_state"))
      (node (ref "IC31") (pin "3") (pinfunction "1D_3") (pintype "input"))
      (node (ref "IC8") (pin "18") (pinfunction "B1_18") (pintype "bidirectional"))
      (node (ref "IC9") (pin "18") (pinfunction "B1_18") (pintype "bidirectional"))
      (node (ref "RN2") (pin "2") (pinfunction "1_2") (pintype "passive"))
    )
    (net (code "35") (name "ADATA9") (class "Default")
      (node (ref "IC11") (pin "4") (pinfunction "A2_4") (pintype "input"))
      (node (ref "IC16") (pin "4") (pinfunction "2D_4") (pintype "input"))
      (node (ref "IC16") (pin "5") (pinfunction "2Q_5") (pintype "tri_state"))
      (node (ref "IC18") (pin "4") (pinfunction "2D_4") (pintype "input"))
      (node (ref "IC18") (pin "5") (pinfunction "2Q_5") (pintype "tri_state"))
      (node (ref "IC22") (pin "4") (pinfunction "2D_4") (pintype "input"))
      (node (ref "IC22") (pin "5") (pinfunction "2Q_5") (pintype "tri_state"))
      (node (ref "IC24") (pin "4") (pinfunction "2D_4") (pintype "input"))
      (node (ref "IC24") (pin "5") (pinfunction "2Q_5") (pintype "tri_state"))
      (node (ref "IC25") (pin "4") (pinfunction "2D_4") (pintype "input"))
      (node (ref "IC25") (pin "5") (pinfunction "2Q_5") (pintype "tri_state"))
      (node (ref "IC27") (pin "4") (pinfunction "2D_4") (pintype "input"))
      (node (ref "IC27") (pin "5") (pinfunction "2Q_5") (pintype "tri_state"))
      (node (ref "IC29") (pin "4") (pinfunction "2D_4") (pintype "input"))
      (node (ref "IC29") (pin "5") (pinfunction "2Q_5") (pintype "tri_state"))
      (node (ref "IC31") (pin "4") (pinfunction "2D_4") (pintype "input"))
      (node (ref "IC31") (pin "5") (pinfunction "2Q_5") (pintype "tri_state"))
      (node (ref "IC8") (pin "17") (pinfunction "B2_17") (pintype "bidirectional"))
      (node (ref "IC9") (pin "17") (pinfunction "B2_17") (pintype "bidirectional"))
      (node (ref "RN2") (pin "3") (pinfunction "1_3") (pintype "passive"))
    )
    (net (code "36") (name "ADATA10") (class "Default")
      (node (ref "IC11") (pin "6") (pinfunction "A3_6") (pintype "input"))
      (node (ref "IC16") (pin "6") (pinfunction "3Q_6") (pintype "tri_state"))
      (node (ref "IC16") (pin "7") (pinfunction "3D_7") (pintype "input"))
      (node (ref "IC18") (pin "6") (pinfunction "3Q_6") (pintype "tri_state"))
      (node (ref "IC18") (pin "7") (pinfunction "3D_7") (pintype "input"))
      (node (ref "IC22") (pin "6") (pinfunction "3Q_6") (pintype "tri_state"))
      (node (ref "IC22") (pin "7") (pinfunction "3D_7") (pintype "input"))
      (node (ref "IC24") (pin "6") (pinfunction "3Q_6") (pintype "tri_state"))
      (node (ref "IC24") (pin "7") (pinfunction "3D_7") (pintype "input"))
      (node (ref "IC25") (pin "6") (pinfunction "3Q_6") (pintype "tri_state"))
      (node (ref "IC25") (pin "7") (pinfunction "3D_7") (pintype "input"))
      (node (ref "IC27") (pin "6") (pinfunction "3Q_6") (pintype "tri_state"))
      (node (ref "IC27") (pin "7") (pinfunction "3D_7") (pintype "input"))
      (node (ref "IC29") (pin "6") (pinfunction "3Q_6") (pintype "tri_state"))
      (node (ref "IC29") (pin "7") (pinfunction "3D_7") (pintype "input"))
      (node (ref "IC31") (pin "6") (pinfunction "3Q_6") (pintype "tri_state"))
      (node (ref "IC31") (pin "7") (pinfunction "3D_7") (pintype "input"))
      (node (ref "IC8") (pin "16") (pinfunction "B3_16") (pintype "bidirectional"))
      (node (ref "IC9") (pin "16") (pinfunction "B3_16") (pintype "bidirectional"))
      (node (ref "RN2") (pin "4") (pinfunction "1_4") (pintype "passive"))
    )
    (net (code "37") (name "ADATA11") (class "Default")
      (node (ref "IC11") (pin "8") (pinfunction "A4_8") (pintype "input"))
      (node (ref "IC16") (pin "8") (pinfunction "4D_8") (pintype "input"))
      (node (ref "IC16") (pin "9") (pinfunction "4Q_9") (pintype "tri_state"))
      (node (ref "IC18") (pin "8") (pinfunction "4D_8") (pintype "input"))
      (node (ref "IC18") (pin "9") (pinfunction "4Q_9") (pintype "tri_state"))
      (node (ref "IC22") (pin "8") (pinfunction "4D_8") (pintype "input"))
      (node (ref "IC22") (pin "9") (pinfunction "4Q_9") (pintype "tri_state"))
      (node (ref "IC24") (pin "8") (pinfunction "4D_8") (pintype "input"))
      (node (ref "IC24") (pin "9") (pinfunction "4Q_9") (pintype "tri_state"))
      (node (ref "IC25") (pin "8") (pinfunction "4D_8") (pintype "input"))
      (node (ref "IC25") (pin "9") (pinfunction "4Q_9") (pintype "tri_state"))
      (node (ref "IC27") (pin "8") (pinfunction "4D_8") (pintype "input"))
      (node (ref "IC27") (pin "9") (pinfunction "4Q_9") (pintype "tri_state"))
      (node (ref "IC29") (pin "8") (pinfunction "4D_8") (pintype "input"))
      (node (ref "IC29") (pin "9") (pinfunction "4Q_9") (pintype "tri_state"))
      (node (ref "IC31") (pin "8") (pinfunction "4D_8") (pintype "input"))
      (node (ref "IC31") (pin "9") (pinfunction "4Q_9") (pintype "tri_state"))
      (node (ref "IC8") (pin "15") (pinfunction "B4_15") (pintype "bidirectional"))
      (node (ref "IC9") (pin "15") (pinfunction "B4_15") (pintype "bidirectional"))
      (node (ref "RN2") (pin "5") (pinfunction "1_5") (pintype "passive"))
    )
    (net (code "38") (name "ADATA12") (class "Default")
      (node (ref "IC11") (pin "11") (pinfunction "A1_11") (pintype "input"))
      (node (ref "IC16") (pin "12") (pinfunction "5Q_12") (pintype "tri_state"))
      (node (ref "IC16") (pin "13") (pinfunction "5D_13") (pintype "input"))
      (node (ref "IC18") (pin "12") (pinfunction "5Q_12") (pintype "tri_state"))
      (node (ref "IC18") (pin "13") (pinfunction "5D_13") (pintype "input"))
      (node (ref "IC22") (pin "12") (pinfunction "5Q_12") (pintype "tri_state"))
      (node (ref "IC22") (pin "13") (pinfunction "5D_13") (pintype "input"))
      (node (ref "IC24") (pin "12") (pinfunction "5Q_12") (pintype "tri_state"))
      (node (ref "IC24") (pin "13") (pinfunction "5D_13") (pintype "input"))
      (node (ref "IC25") (pin "12") (pinfunction "5Q_12") (pintype "tri_state"))
      (node (ref "IC25") (pin "13") (pinfunction "5D_13") (pintype "input"))
      (node (ref "IC27") (pin "12") (pinfunction "5Q_12") (pintype "tri_state"))
      (node (ref "IC27") (pin "13") (pinfunction "5D_13") (pintype "input"))
      (node (ref "IC29") (pin "12") (pinfunction "5Q_12") (pintype "tri_state"))
      (node (ref "IC29") (pin "13") (pinfunction "5D_13") (pintype "input"))
      (node (ref "IC31") (pin "12") (pinfunction "5Q_12") (pintype "tri_state"))
      (node (ref "IC31") (pin "13") (pinfunction "5D_13") (pintype "input"))
      (node (ref "IC8") (pin "14") (pinfunction "B5_14") (pintype "bidirectional"))
      (node (ref "IC9") (pin "14") (pinfunction "B5_14") (pintype "bidirectional"))
      (node (ref "RN2") (pin "6") (pinfunction "1_6") (pintype "passive"))
    )
    (net (code "39") (name "ADATA13") (class "Default")
      (node (ref "IC11") (pin "13") (pinfunction "A2_13") (pintype "input"))
      (node (ref "IC16") (pin "14") (pinfunction "6D_14") (pintype "input"))
      (node (ref "IC16") (pin "15") (pinfunction "6Q_15") (pintype "tri_state"))
      (node (ref "IC18") (pin "14") (pinfunction "6D_14") (pintype "input"))
      (node (ref "IC18") (pin "15") (pinfunction "6Q_15") (pintype "tri_state"))
      (node (ref "IC22") (pin "14") (pinfunction "6D_14") (pintype "input"))
      (node (ref "IC22") (pin "15") (pinfunction "6Q_15") (pintype "tri_state"))
      (node (ref "IC24") (pin "14") (pinfunction "6D_14") (pintype "input"))
      (node (ref "IC24") (pin "15") (pinfunction "6Q_15") (pintype "tri_state"))
      (node (ref "IC25") (pin "14") (pinfunction "6D_14") (pintype "input"))
      (node (ref "IC25") (pin "15") (pinfunction "6Q_15") (pintype "tri_state"))
      (node (ref "IC27") (pin "14") (pinfunction "6D_14") (pintype "input"))
      (node (ref "IC27") (pin "15") (pinfunction "6Q_15") (pintype "tri_state"))
      (node (ref "IC29") (pin "14") (pinfunction "6D_14") (pintype "input"))
      (node (ref "IC29") (pin "15") (pinfunction "6Q_15") (pintype "tri_state"))
      (node (ref "IC31") (pin "14") (pinfunction "6D_14") (pintype "input"))
      (node (ref "IC31") (pin "15") (pinfunction "6Q_15") (pintype "tri_state"))
      (node (ref "IC8") (pin "13") (pinfunction "B6_13") (pintype "bidirectional"))
      (node (ref "IC9") (pin "13") (pinfunction "B6_13") (pintype "bidirectional"))
      (node (ref "RN2") (pin "7") (pinfunction "1_7") (pintype "passive"))
    )
    (net (code "40") (name "ADATA14") (class "Default")
      (node (ref "IC11") (pin "15") (pinfunction "A3_15") (pintype "input"))
      (node (ref "IC16") (pin "16") (pinfunction "7Q_16") (pintype "tri_state"))
      (node (ref "IC16") (pin "17") (pinfunction "7D_17") (pintype "input"))
      (node (ref "IC18") (pin "16") (pinfunction "7Q_16") (pintype "tri_state"))
      (node (ref "IC18") (pin "17") (pinfunction "7D_17") (pintype "input"))
      (node (ref "IC22") (pin "16") (pinfunction "7Q_16") (pintype "tri_state"))
      (node (ref "IC22") (pin "17") (pinfunction "7D_17") (pintype "input"))
      (node (ref "IC24") (pin "16") (pinfunction "7Q_16") (pintype "tri_state"))
      (node (ref "IC24") (pin "17") (pinfunction "7D_17") (pintype "input"))
      (node (ref "IC25") (pin "16") (pinfunction "7Q_16") (pintype "tri_state"))
      (node (ref "IC25") (pin "17") (pinfunction "7D_17") (pintype "input"))
      (node (ref "IC27") (pin "16") (pinfunction "7Q_16") (pintype "tri_state"))
      (node (ref "IC27") (pin "17") (pinfunction "7D_17") (pintype "input"))
      (node (ref "IC29") (pin "16") (pinfunction "7Q_16") (pintype "tri_state"))
      (node (ref "IC29") (pin "17") (pinfunction "7D_17") (pintype "input"))
      (node (ref "IC31") (pin "16") (pinfunction "7Q_16") (pintype "tri_state"))
      (node (ref "IC31") (pin "17") (pinfunction "7D_17") (pintype "input"))
      (node (ref "IC8") (pin "12") (pinfunction "B7_12") (pintype "bidirectional"))
      (node (ref "IC9") (pin "12") (pinfunction "B7_12") (pintype "bidirectional"))
      (node (ref "RN2") (pin "8") (pinfunction "1_8") (pintype "passive"))
    )
    (net (code "41") (name "ADATA15") (class "Default")
      (node (ref "IC11") (pin "17") (pinfunction "A4_17") (pintype "input"))
      (node (ref "IC16") (pin "18") (pinfunction "8D_18") (pintype "input"))
      (node (ref "IC16") (pin "19") (pinfunction "8Q_19") (pintype "tri_state"))
      (node (ref "IC18") (pin "18") (pinfunction "8D_18") (pintype "input"))
      (node (ref "IC18") (pin "19") (pinfunction "8Q_19") (pintype "tri_state"))
      (node (ref "IC22") (pin "18") (pinfunction "8D_18") (pintype "input"))
      (node (ref "IC22") (pin "19") (pinfunction "8Q_19") (pintype "tri_state"))
      (node (ref "IC24") (pin "18") (pinfunction "8D_18") (pintype "input"))
      (node (ref "IC24") (pin "19") (pinfunction "8Q_19") (pintype "tri_state"))
      (node (ref "IC25") (pin "18") (pinfunction "8D_18") (pintype "input"))
      (node (ref "IC25") (pin "19") (pinfunction "8Q_19") (pintype "tri_state"))
      (node (ref "IC27") (pin "18") (pinfunction "8D_18") (pintype "input"))
      (node (ref "IC27") (pin "19") (pinfunction "8Q_19") (pintype "tri_state"))
      (node (ref "IC29") (pin "18") (pinfunction "8D_18") (pintype "input"))
      (node (ref "IC29") (pin "19") (pinfunction "8Q_19") (pintype "tri_state"))
      (node (ref "IC31") (pin "18") (pinfunction "8D_18") (pintype "input"))
      (node (ref "IC31") (pin "19") (pinfunction "8Q_19") (pintype "tri_state"))
      (node (ref "IC8") (pin "11") (pinfunction "B8_11") (pintype "bidirectional"))
      (node (ref "IC9") (pin "11") (pinfunction "B8_11") (pintype "bidirectional"))
      (node (ref "RN2") (pin "9") (pinfunction "1_9") (pintype "passive"))
    )
    (net (code "42") (name "ADDR-ID0") (class "Default")
      (node (ref "X3") (pin "B9") (pinfunction "B_B9") (pintype "passive"))
    )
    (net (code "43") (name "ADDR-ID1") (class "Default")
      (node (ref "X3") (pin "B10") (pinfunction "B_B10") (pintype "passive"))
    )
    (net (code "44") (name "ADDR-REG-ADDR-RD") (class "Default")
      (node (ref "X3") (pin "C10") (pinfunction "B_C10") (pintype "passive"))
    )
    (net (code "45") (name "ADDR-REG-DATA-RD-HI") (class "Default")
      (node (ref "X3") (pin "C9") (pinfunction "B_C9") (pintype "passive"))
    )
    (net (code "46") (name "ADDR-REG-DATA-RD-LO") (class "Default")
      (node (ref "X3") (pin "C8") (pinfunction "B_C8") (pintype "passive"))
    )
    (net (code "47") (name "ADDR-REG-DN") (class "Default")
      (node (ref "X3") (pin "C13") (pinfunction "B_C13") (pintype "passive"))
    )
    (net (code "48") (name "ADDR-REG-FUNC") (class "Default")
      (node (ref "X3") (pin "C7") (pinfunction "B_C7") (pintype "passive"))
    )
    (net (code "49") (name "ADDR-REG-LD-HI") (class "Default")
      (node (ref "X3") (pin "C12") (pinfunction "B_C12") (pintype "passive"))
    )
    (net (code "50") (name "ADDR-REG-LD-LO") (class "Default")
      (node (ref "X3") (pin "C11") (pinfunction "B_C11") (pintype "passive"))
    )
    (net (code "51") (name "ADDR-REG-UP") (class "Default")
      (node (ref "X3") (pin "C14") (pinfunction "B_C14") (pintype "passive"))
    )
    (net (code "52") (name "ADDR0") (class "Default")
      (node (ref "X3") (pin "A3") (pinfunction "B_A3") (pintype "passive"))
    )
    (net (code "53") (name "ADDR1") (class "Default")
      (node (ref "X3") (pin "A4") (pinfunction "B_A4") (pintype "passive"))
    )
    (net (code "54") (name "ADDR2") (class "Default")
      (node (ref "X3") (pin "A5") (pinfunction "B_A5") (pintype "passive"))
    )
    (net (code "55") (name "ADDR3") (class "Default")
      (node (ref "X3") (pin "A6") (pinfunction "B_A6") (pintype "passive"))
    )
    (net (code "56") (name "ADDR4") (class "Default")
      (node (ref "X3") (pin "A7") (pinfunction "B_A7") (pintype "passive"))
    )
    (net (code "57") (name "ADDR5") (class "Default")
      (node (ref "X3") (pin "A8") (pinfunction "B_A8") (pintype "passive"))
    )
    (net (code "58") (name "ADDR6") (class "Default")
      (node (ref "X3") (pin "A9") (pinfunction "B_A9") (pintype "passive"))
    )
    (net (code "59") (name "ADDR7") (class "Default")
      (node (ref "X3") (pin "A10") (pinfunction "B_A10") (pintype "passive"))
    )
    (net (code "60") (name "ADDR8") (class "Default")
      (node (ref "X3") (pin "A11") (pinfunction "B_A11") (pintype "passive"))
    )
    (net (code "61") (name "ADDR9") (class "Default")
      (node (ref "X3") (pin "A12") (pinfunction "B_A12") (pintype "passive"))
    )
    (net (code "62") (name "ADDR10") (class "Default")
      (node (ref "X3") (pin "A13") (pinfunction "B_A13") (pintype "passive"))
    )
    (net (code "63") (name "ADDR11") (class "Default")
      (node (ref "X3") (pin "A14") (pinfunction "B_A14") (pintype "passive"))
    )
    (net (code "64") (name "ADDR12") (class "Default")
      (node (ref "X3") (pin "A15") (pinfunction "B_A15") (pintype "passive"))
    )
    (net (code "65") (name "ADDR13") (class "Default")
      (node (ref "X3") (pin "A16") (pinfunction "B_A16") (pintype "passive"))
    )
    (net (code "66") (name "ADDR14") (class "Default")
      (node (ref "X3") (pin "A17") (pinfunction "B_A17") (pintype "passive"))
    )
    (net (code "67") (name "ADDR15") (class "Default")
      (node (ref "X3") (pin "A18") (pinfunction "B_A18") (pintype "passive"))
    )
    (net (code "68") (name "ALU-FUNC") (class "Default")
      (node (ref "X3") (pin "C15") (pinfunction "B_C15") (pintype "passive"))
    )
    (net (code "69") (name "ALU0") (class "Default")
      (node (ref "X3") (pin "C16") (pinfunction "B_C16") (pintype "passive"))
    )
    (net (code "70") (name "ALU1") (class "Default")
      (node (ref "X3") (pin "C17") (pinfunction "B_C17") (pintype "passive"))
    )
    (net (code "71") (name "ALU2") (class "Default")
      (node (ref "X3") (pin "C18") (pinfunction "B_C18") (pintype "passive"))
    )
    (net (code "72") (name "ALU3") (class "Default")
      (node (ref "X3") (pin "C19") (pinfunction "B_C19") (pintype "passive"))
    )
    (net (code "73") (name "BR-COND") (class "Default")
      (node (ref "X3") (pin "C24") (pinfunction "B_C24") (pintype "passive"))
    )
    (net (code "74") (name "BUS-DIR") (class "Default")
      (node (ref "IC1") (pin "10") (pinfunction "O_10") (pintype "output"))
      (node (ref "IC7") (pin "1") (pinfunction "DIR_1") (pintype "input"))
      (node (ref "IC8") (pin "1") (pinfunction "DIR_1") (pintype "input"))
      (node (ref "IC9") (pin "1") (pinfunction "DIR_1") (pintype "input"))
    )
    (net (code "75") (name "CLK0H") (class "Default")
      (node (ref "IC14") (pin "4") (pinfunction "O_4") (pintype "output"))
      (node (ref "IC16") (pin "11") (pinfunction "CLK_11") (pintype "input"))
      (node (ref "IC34") (pin "15") (pinfunction "A3_15") (pintype "input"))
    )
    (net (code "76") (name "CLK0L") (class "Default")
      (node (ref "IC14") (pin "1") (pinfunction "O_1") (pintype "output"))
      (node (ref "IC15") (pin "11") (pinfunction "CLK_11") (pintype "input"))
      (node (ref "IC34") (pin "17") (pinfunction "A4_17") (pintype "input"))
    )
    (net (code "77") (name "CLK1H") (class "Default")
      (node (ref "IC14") (pin "13") (pinfunction "O_13") (pintype "output"))
      (node (ref "IC18") (pin "11") (pinfunction "CLK_11") (pintype "input"))
      (node (ref "IC34") (pin "11") (pinfunction "A1_11") (pintype "input"))
    )
    (net (code "78") (name "CLK1L") (class "Default")
      (node (ref "IC14") (pin "10") (pinfunction "O_10") (pintype "output"))
      (node (ref "IC17") (pin "11") (pinfunction "CLK_11") (pintype "input"))
      (node (ref "IC34") (pin "13") (pinfunction "A2_13") (pintype "input"))
    )
    (net (code "79") (name "CLK2H") (class "Default")
      (node (ref "IC20") (pin "4") (pinfunction "O_4") (pintype "output"))
      (node (ref "IC22") (pin "11") (pinfunction "CLK_11") (pintype "input"))
      (node (ref "IC33") (pin "4") (pinfunction "A2_4") (pintype "input"))
    )
    (net (code "80") (name "CLK2L") (class "Default")
      (node (ref "IC20") (pin "1") (pinfunction "O_1") (pintype "output"))
      (node (ref "IC21") (pin "11") (pinfunction "CLK_11") (pintype "input"))
      (node (ref "IC33") (pin "2") (pinfunction "A1_2") (pintype "input"))
    )
    (net (code "81") (name "CLK3H") (class "Default")
      (node (ref "IC20") (pin "13") (pinfunction "O_13") (pintype "output"))
      (node (ref "IC24") (pin "11") (pinfunction "CLK_11") (pintype "input"))
      (node (ref "IC33") (pin "8") (pinfunction "A4_8") (pintype "input"))
    )
    (net (code "82") (name "CLK3L") (class "Default")
      (node (ref "IC20") (pin "10") (pinfunction "O_10") (pintype "output"))
      (node (ref "IC23") (pin "11") (pinfunction "CLK_11") (pintype "input"))
      (node (ref "IC33") (pin "6") (pinfunction "A3_6") (pintype "input"))
    )
    (net (code "83") (name "CLK4H") (class "Default")
      (node (ref "IC25") (pin "11") (pinfunction "CLK_11") (pintype "input"))
      (node (ref "IC34") (pin "6") (pinfunction "A3_6") (pintype "input"))
      (node (ref "IC35") (pin "4") (pinfunction "O_4") (pintype "output"))
    )
    (net (code "84") (name "CLK4L") (class "Default")
      (node (ref "IC10") (pin "11") (pinfunction "CLK_11") (pintype "input"))
      (node (ref "IC34") (pin "8") (pinfunction "A4_8") (pintype "input"))
      (node (ref "IC35") (pin "1") (pinfunction "O_1") (pintype "output"))
    )
    (net (code "85") (name "CLK5H") (class "Default")
      (node (ref "IC29") (pin "11") (pinfunction "CLK_11") (pintype "input"))
      (node (ref "IC34") (pin "2") (pinfunction "A1_2") (pintype "input"))
      (node (ref "IC35") (pin "13") (pinfunction "O_13") (pintype "output"))
    )
    (net (code "86") (name "CLK5L") (class "Default")
      (node (ref "IC28") (pin "11") (pinfunction "CLK_11") (pintype "input"))
      (node (ref "IC34") (pin "4") (pinfunction "A2_4") (pintype "input"))
      (node (ref "IC35") (pin "10") (pinfunction "O_10") (pintype "output"))
    )
    (net (code "87") (name "CLK6H") (class "Default")
      (node (ref "IC27") (pin "11") (pinfunction "CLK_11") (pintype "input"))
      (node (ref "IC33") (pin "13") (pinfunction "A2_13") (pintype "input"))
      (node (ref "IC38") (pin "4") (pinfunction "O_4") (pintype "output"))
    )
    (net (code "88") (name "CLK6L") (class "Default")
      (node (ref "IC26") (pin "11") (pinfunction "CLK_11") (pintype "input"))
      (node (ref "IC33") (pin "11") (pinfunction "A1_11") (pintype "input"))
      (node (ref "IC38") (pin "1") (pinfunction "O_1") (pintype "output"))
    )
    (net (code "89") (name "CLK7H") (class "Default")
      (node (ref "IC31") (pin "11") (pinfunction "CLK_11") (pintype "input"))
      (node (ref "IC33") (pin "17") (pinfunction "A4_17") (pintype "input"))
      (node (ref "IC38") (pin "13") (pinfunction "O_13") (pintype "output"))
    )
    (net (code "90") (name "CLK7L") (class "Default")
      (node (ref "IC30") (pin "11") (pinfunction "CLK_11") (pintype "input"))
      (node (ref "IC33") (pin "15") (pinfunction "A3_15") (pintype "input"))
      (node (ref "IC38") (pin "10") (pinfunction "O_10") (pintype "output"))
    )
    (net (code "91") (name "DATA0") (class "Default")
      (node (ref "IC7") (pin "2") (pinfunction "A1_2") (pintype "bidirectional"))
      (node (ref "IC9") (pin "2") (pinfunction "A1_2") (pintype "bidirectional"))
      (node (ref "X3") (pin "A19") (pinfunction "B_A19") (pintype "passive"))
    )
    (net (code "92") (name "DATA1") (class "Default")
      (node (ref "IC7") (pin "3") (pinfunction "A2_3") (pintype "bidirectional"))
      (node (ref "IC9") (pin "3") (pinfunction "A2_3") (pintype "bidirectional"))
      (node (ref "X3") (pin "A20") (pinfunction "B_A20") (pintype "passive"))
    )
    (net (code "93") (name "DATA2") (class "Default")
      (node (ref "IC7") (pin "4") (pinfunction "A3_4") (pintype "bidirectional"))
      (node (ref "IC9") (pin "4") (pinfunction "A3_4") (pintype "bidirectional"))
      (node (ref "X3") (pin "A21") (pinfunction "B_A21") (pintype "passive"))
    )
    (net (code "94") (name "DATA3") (class "Default")
      (node (ref "IC7") (pin "5") (pinfunction "A4_5") (pintype "bidirectional"))
      (node (ref "IC9") (pin "5") (pinfunction "A4_5") (pintype "bidirectional"))
      (node (ref "X3") (pin "A22") (pinfunction "B_A22") (pintype "passive"))
    )
    (net (code "95") (name "DATA4") (class "Default")
      (node (ref "IC7") (pin "6") (pinfunction "A5_6") (pintype "bidirectional"))
      (node (ref "IC9") (pin "6") (pinfunction "A5_6") (pintype "bidirectional"))
      (node (ref "X3") (pin "A23") (pinfunction "B_A23") (pintype "passive"))
    )
    (net (code "96") (name "DATA5") (class "Default")
      (node (ref "IC7") (pin "7") (pinfunction "A6_7") (pintype "bidirectional"))
      (node (ref "IC9") (pin "7") (pinfunction "A6_7") (pintype "bidirectional"))
      (node (ref "X3") (pin "A24") (pinfunction "B_A24") (pintype "passive"))
    )
    (net (code "97") (name "DATA6") (class "Default")
      (node (ref "IC7") (pin "8") (pinfunction "A7_8") (pintype "bidirectional"))
      (node (ref "IC9") (pin "8") (pinfunction "A7_8") (pintype "bidirectional"))
      (node (ref "X3") (pin "A25") (pinfunction "B_A25") (pintype "passive"))
    )
    (net (code "98") (name "DATA7") (class "Default")
      (node (ref "IC7") (pin "9") (pinfunction "A8_9") (pintype "bidirectional"))
      (node (ref "IC9") (pin "9") (pinfunction "A8_9") (pintype "bidirectional"))
      (node (ref "X3") (pin "A26") (pinfunction "B_A26") (pintype "passive"))
    )
    (net (code "99") (name "DATA8") (class "Default")
      (node (ref "IC8") (pin "2") (pinfunction "A1_2") (pintype "bidirectional"))
      (node (ref "X3") (pin "A27") (pinfunction "B_A27") (pintype "passive"))
    )
    (net (code "100") (name "DATA9") (class "Default")
      (node (ref "IC8") (pin "3") (pinfunction "A2_3") (pintype "bidirectional"))
      (node (ref "X3") (pin "A28") (pinfunction "B_A28") (pintype "passive"))
    )
    (net (code "101") (name "DATA10") (class "Default")
      (node (ref "IC8") (pin "4") (pinfunction "A3_4") (pintype "bidirectional"))
      (node (ref "X3") (pin "A29") (pinfunction "B_A29") (pintype "passive"))
    )
    (net (code "102") (name "DATA11") (class "Default")
      (node (ref "IC8") (pin "5") (pinfunction "A4_5") (pintype "bidirectional"))
      (node (ref "X3") (pin "A30") (pinfunction "B_A30") (pintype "passive"))
    )
    (net (code "103") (name "DATA12") (class "Default")
      (node (ref "IC8") (pin "6") (pinfunction "A5_6") (pintype "bidirectional"))
      (node (ref "X3") (pin "B3") (pinfunction "B_B3") (pintype "passive"))
    )
    (net (code "104") (name "DATA13") (class "Default")
      (node (ref "IC8") (pin "7") (pinfunction "A6_7") (pintype "bidirectional"))
      (node (ref "X3") (pin "B4") (pinfunction "B_B4") (pintype "passive"))
    )
    (net (code "105") (name "DATA14") (class "Default")
      (node (ref "IC8") (pin "8") (pinfunction "A7_8") (pintype "bidirectional"))
      (node (ref "X3") (pin "B5") (pinfunction "B_B5") (pintype "passive"))
    )
    (net (code "106") (name "DATA15") (class "Default")
      (node (ref "IC8") (pin "9") (pinfunction "A8_9") (pintype "bidirectional"))
      (node (ref "X3") (pin "B6") (pinfunction "B_B6") (pintype "passive"))
    )
    (net (code "107") (name "FP-ADATA0") (class "Default")
      (node (ref "IC12") (pin "18") (pinfunction "Y1_18") (pintype "tri_state"))
      (node (ref "JP6") (pin "3") (pinfunction "3_3") (pintype "passive"))
    )
    (net (code "108") (name "FP-ADATA1") (class "Default")
      (node (ref "IC12") (pin "16") (pinfunction "Y2_16") (pintype "tri_state"))
      (node (ref "JP6") (pin "5") (pinfunction "5_5") (pintype "passive"))
    )
    (net (code "109") (name "FP-ADATA2") (class "Default")
      (node (ref "IC12") (pin "14") (pinfunction "Y3_14") (pintype "tri_state"))
      (node (ref "JP6") (pin "7") (pinfunction "7_7") (pintype "passive"))
    )
    (net (code "110") (name "FP-ADATA3") (class "Default")
      (node (ref "IC12") (pin "12") (pinfunction "Y4_12") (pintype "tri_state"))
      (node (ref "JP6") (pin "9") (pinfunction "9_9") (pintype "passive"))
    )
    (net (code "111") (name "FP-ADATA4") (class "Default")
      (node (ref "IC12") (pin "9") (pinfunction "Y1_9") (pintype "tri_state"))
      (node (ref "JP6") (pin "11") (pinfunction "11_11") (pintype "passive"))
    )
    (net (code "112") (name "FP-ADATA5") (class "Default")
      (node (ref "IC12") (pin "7") (pinfunction "Y2_7") (pintype "tri_state"))
      (node (ref "JP6") (pin "13") (pinfunction "13_13") (pintype "passive"))
    )
    (net (code "113") (name "FP-ADATA6") (class "Default")
      (node (ref "IC12") (pin "5") (pinfunction "Y3_5") (pintype "tri_state"))
      (node (ref "JP6") (pin "15") (pinfunction "15_15") (pintype "passive"))
    )
    (net (code "114") (name "FP-ADATA7") (class "Default")
      (node (ref "IC12") (pin "3") (pinfunction "Y4_3") (pintype "tri_state"))
      (node (ref "JP6") (pin "17") (pinfunction "17_17") (pintype "passive"))
    )
    (net (code "115") (name "FP-ADATA8") (class "Default")
      (node (ref "IC11") (pin "18") (pinfunction "Y1_18") (pintype "tri_state"))
      (node (ref "JP6") (pin "4") (pinfunction "4_4") (pintype "passive"))
    )
    (net (code "116") (name "FP-ADATA9") (class "Default")
      (node (ref "IC11") (pin "16") (pinfunction "Y2_16") (pintype "tri_state"))
      (node (ref "JP6") (pin "6") (pinfunction "6_6") (pintype "passive"))
    )
    (net (code "117") (name "FP-ADATA10") (class "Default")
      (node (ref "IC11") (pin "14") (pinfunction "Y3_14") (pintype "tri_state"))
      (node (ref "JP6") (pin "8") (pinfunction "8_8") (pintype "passive"))
    )
    (net (code "118") (name "FP-ADATA11") (class "Default")
      (node (ref "IC11") (pin "12") (pinfunction "Y4_12") (pintype "tri_state"))
      (node (ref "JP6") (pin "10") (pinfunction "10_10") (pintype "passive"))
    )
    (net (code "119") (name "FP-ADATA12") (class "Default")
      (node (ref "IC11") (pin "9") (pinfunction "Y1_9") (pintype "tri_state"))
      (node (ref "JP6") (pin "12") (pinfunction "12_12") (pintype "passive"))
    )
    (net (code "120") (name "FP-ADATA13") (class "Default")
      (node (ref "IC11") (pin "7") (pinfunction "Y2_7") (pintype "tri_state"))
      (node (ref "JP6") (pin "14") (pinfunction "14_14") (pintype "passive"))
    )
    (net (code "121") (name "FP-ADATA14") (class "Default")
      (node (ref "IC11") (pin "5") (pinfunction "Y3_5") (pintype "tri_state"))
      (node (ref "JP6") (pin "16") (pinfunction "16_16") (pintype "passive"))
    )
    (net (code "122") (name "FP-ADATA15") (class "Default")
      (node (ref "IC11") (pin "3") (pinfunction "Y4_3") (pintype "tri_state"))
      (node (ref "JP6") (pin "18") (pinfunction "18_18") (pintype "passive"))
    )
    (net (code "123") (name "FP-CLK0H") (class "Default")
      (node (ref "IC34") (pin "5") (pinfunction "Y3_5") (pintype "tri_state"))
      (node (ref "JP6") (pin "23") (pinfunction "23_23") (pintype "passive"))
    )
    (net (code "124") (name "FP-CLK0L") (class "Default")
      (node (ref "IC34") (pin "3") (pinfunction "Y4_3") (pintype "tri_state"))
      (node (ref "JP6") (pin "25") (pinfunction "25_25") (pintype "passive"))
    )
    (net (code "125") (name "FP-CLK1H") (class "Default")
      (node (ref "IC34") (pin "9") (pinfunction "Y1_9") (pintype "tri_state"))
      (node (ref "JP6") (pin "19") (pinfunction "19_19") (pintype "passive"))
    )
    (net (code "126") (name "FP-CLK1L") (class "Default")
      (node (ref "IC34") (pin "7") (pinfunction "Y2_7") (pintype "tri_state"))
      (node (ref "JP6") (pin "21") (pinfunction "21_21") (pintype "passive"))
    )
    (net (code "127") (name "FP-CLK2H") (class "Default")
      (node (ref "IC33") (pin "16") (pinfunction "Y2_16") (pintype "tri_state"))
      (node (ref "JP6") (pin "24") (pinfunction "24_24") (pintype "passive"))
    )
    (net (code "128") (name "FP-CLK2L") (class "Default")
      (node (ref "IC33") (pin "18") (pinfunction "Y1_18") (pintype "tri_state"))
      (node (ref "JP6") (pin "26") (pinfunction "26_26") (pintype "passive"))
    )
    (net (code "129") (name "FP-CLK3H") (class "Default")
      (node (ref "IC33") (pin "12") (pinfunction "Y4_12") (pintype "tri_state"))
      (node (ref "JP6") (pin "20") (pinfunction "20_20") (pintype "passive"))
    )
    (net (code "130") (name "FP-CLK3L") (class "Default")
      (node (ref "IC33") (pin "14") (pinfunction "Y3_14") (pintype "tri_state"))
      (node (ref "JP6") (pin "22") (pinfunction "22_22") (pintype "passive"))
    )
    (net (code "131") (name "FP-CLK4H") (class "Default")
      (node (ref "IC34") (pin "14") (pinfunction "Y3_14") (pintype "tri_state"))
      (node (ref "JP6") (pin "31") (pinfunction "31_31") (pintype "passive"))
    )
    (net (code "132") (name "FP-CLK4L") (class "Default")
      (node (ref "IC34") (pin "12") (pinfunction "Y4_12") (pintype "tri_state"))
      (node (ref "JP6") (pin "33") (pinfunction "33_33") (pintype "passive"))
    )
    (net (code "133") (name "FP-CLK5H") (class "Default")
      (node (ref "IC34") (pin "18") (pinfunction "Y1_18") (pintype "tri_state"))
      (node (ref "JP6") (pin "27") (pinfunction "27_27") (pintype "passive"))
    )
    (net (code "134") (name "FP-CLK5L") (class "Default")
      (node (ref "IC34") (pin "16") (pinfunction "Y2_16") (pintype "tri_state"))
      (node (ref "JP6") (pin "29") (pinfunction "29_29") (pintype "passive"))
    )
    (net (code "135") (name "FP-CLK6H") (class "Default")
      (node (ref "IC33") (pin "7") (pinfunction "Y2_7") (pintype "tri_state"))
      (node (ref "JP6") (pin "32") (pinfunction "32_32") (pintype "passive"))
    )
    (net (code "136") (name "FP-CLK6L") (class "Default")
      (node (ref "IC33") (pin "9") (pinfunction "Y1_9") (pintype "tri_state"))
      (node (ref "JP6") (pin "34") (pinfunction "34_34") (pintype "passive"))
    )
    (net (code "137") (name "FP-CLK7H") (class "Default")
      (node (ref "IC33") (pin "3") (pinfunction "Y4_3") (pintype "tri_state"))
      (node (ref "JP6") (pin "28") (pinfunction "28_28") (pintype "passive"))
    )
    (net (code "138") (name "FP-CLK7L") (class "Default")
      (node (ref "IC33") (pin "5") (pinfunction "Y3_5") (pintype "tri_state"))
      (node (ref "JP6") (pin "30") (pinfunction "30_30") (pintype "passive"))
    )
    (net (code "139") (name "GND") (class "Default")
      (node (ref "C1") (pin "2") (pinfunction "2_2") (pintype "passive"))
      (node (ref "C10") (pin "2") (pinfunction "2_2") (pintype "passive"))
      (node (ref "C11") (pin "2") (pinfunction "2_2") (pintype "passive"))
      (node (ref "C12") (pin "2") (pinfunction "2_2") (pintype "passive"))
      (node (ref "C13") (pin "2") (pinfunction "2_2") (pintype "passive"))
      (node (ref "C14") (pin "2") (pinfunction "2_2") (pintype "passive"))
      (node (ref "C15") (pin "2") (pinfunction "2_2") (pintype "passive"))
      (node (ref "C16") (pin "2") (pinfunction "2_2") (pintype "passive"))
      (node (ref "C17") (pin "2") (pinfunction "2_2") (pintype "passive"))
      (node (ref "C18") (pin "2") (pinfunction "2_2") (pintype "passive"))
      (node (ref "C19") (pin "2") (pinfunction "2_2") (pintype "passive"))
      (node (ref "C2") (pin "2") (pinfunction "2_2") (pintype "passive"))
      (node (ref "C20") (pin "2") (pinfunction "2_2") (pintype "passive"))
      (node (ref "C21") (pin "2") (pinfunction "2_2") (pintype "passive"))
      (node (ref "C22") (pin "2") (pinfunction "2_2") (pintype "passive"))
      (node (ref "C23") (pin "2") (pinfunction "2_2") (pintype "passive"))
      (node (ref "C24") (pin "2") (pinfunction "2_2") (pintype "passive"))
      (node (ref "C25") (pin "2") (pinfunction "2_2") (pintype "passive"))
      (node (ref "C26") (pin "2") (pinfunction "2_2") (pintype "passive"))
      (node (ref "C27") (pin "2") (pinfunction "2_2") (pintype "passive"))
      (node (ref "C28") (pin "2") (pinfunction "2_2") (pintype "passive"))
      (node (ref "C29") (pin "2") (pinfunction "2_2") (pintype "passive"))
      (node (ref "C3") (pin "2") (pinfunction "2_2") (pintype "passive"))
      (node (ref "C30") (pin "2") (pinfunction "2_2") (pintype "passive"))
      (node (ref "C31") (pin "2") (pinfunction "2_2") (pintype "passive"))
      (node (ref "C32") (pin "2") (pinfunction "2_2") (pintype "passive"))
      (node (ref "C33") (pin "2") (pinfunction "2_2") (pintype "passive"))
      (node (ref "C34") (pin "2") (pinfunction "2_2") (pintype "passive"))
      (node (ref "C35") (pin "2") (pinfunction "2_2") (pintype "passive"))
      (node (ref "C36") (pin "2") (pinfunction "2_2") (pintype "passive"))
      (node (ref "C37") (pin "2") (pinfunction "2_2") (pintype "passive"))
      (node (ref "C4") (pin "2") (pinfunction "2_2") (pintype "passive"))
      (node (ref "C5") (pin "2") (pinfunction "2_2") (pintype "passive"))
      (node (ref "C6") (pin "2") (pinfunction "2_2") (pintype "passive"))
      (node (ref "C7") (pin "2") (pinfunction "2_2") (pintype "passive"))
      (node (ref "C8") (pin "2") (pinfunction "2_2") (pintype "passive"))
      (node (ref "C9") (pin "2") (pinfunction "2_2") (pintype "passive"))
      (node (ref "IC5") (pin "10") (pinfunction "I1_10") (pintype "input"))
      (node (ref "IC5") (pin "12") (pinfunction "I0_12") (pintype "input"))
      (node (ref "IC5") (pin "13") (pinfunction "I1_13") (pintype "input"))
      (node (ref "IC5") (pin "4") (pinfunction "I0_4") (pintype "input"))
      (node (ref "IC5") (pin "5") (pinfunction "I1_5") (pintype "input"))
      (node (ref "IC5") (pin "9") (pinfunction "I0_9") (pintype "input"))
      (node (ref "J1") (pin "2") (pinfunction "2_2") (pintype "passive"))
      (node (ref "JP6") (pin "39") (pinfunction "39_39") (pintype "passive"))
      (node (ref "JP6") (pin "40") (pinfunction "40_40") (pintype "passive"))
      (node (ref "PWR1") (pin "K") (pinfunction "C_K") (pintype "passive"))
      (node (ref "X3") (pin "A1") (pinfunction "B_A1") (pintype "passive"))
      (node (ref "X3") (pin "A32") (pinfunction "B_A32") (pintype "passive"))
      (node (ref "X3") (pin "B1") (pinfunction "B_B1") (pintype "passive"))
      (node (ref "X3") (pin "B32") (pinfunction "B_B32") (pintype "passive"))
      (node (ref "X3") (pin "C1") (pinfunction "B_C1") (pintype "passive"))
      (node (ref "X3") (pin "C32") (pinfunction "B_C32") (pintype "passive"))
    )
    (net (code "140") (name "H{slash}L-SWAP") (class "Default")
      (node (ref "IC1") (pin "13") (pinfunction "I_13") (pintype "input"))
      (node (ref "IC6") (pin "10") (pinfunction "I1_10") (pintype "input"))
      (node (ref "X3") (pin "C25") (pinfunction "B_C25") (pintype "passive"))
    )
    (net (code "141") (name "IN") (class "Default")
      (node (ref "X3") (pin "C26") (pinfunction "B_C26") (pintype "passive"))
    )
    (net (code "142") (name "INT") (class "Default")
      (node (ref "X3") (pin "B29") (pinfunction "B_B29") (pintype "passive"))
    )
    (net (code "143") (name "INTA") (class "Default")
      (node (ref "X3") (pin "B30") (pinfunction "B_B30") (pintype "passive"))
    )
    (net (code "144") (name "I{slash}O-ADDR") (class "Default")
      (node (ref "X3") (pin "B28") (pinfunction "B_B28") (pintype "passive"))
    )
    (net (code "145") (name "I{slash}O-RD") (class "Default")
      (node (ref "X3") (pin "B27") (pinfunction "B_B27") (pintype "passive"))
    )
    (net (code "146") (name "I{slash}O-WR") (class "Default")
      (node (ref "X3") (pin "B26") (pinfunction "B_B26") (pintype "passive"))
    )
    (net (code "147") (name "MEM-RD") (class "Default")
      (node (ref "X3") (pin "B25") (pinfunction "B_B25") (pintype "passive"))
    )
    (net (code "148") (name "MEM-WR") (class "Default")
      (node (ref "X3") (pin "B24") (pinfunction "B_B24") (pintype "passive"))
    )
    (net (code "149") (name "Net-(IC1F-O)") (class "Default")
      (node (ref "IC1") (pin "12") (pinfunction "O_12") (pintype "output"))
      (node (ref "IC6") (pin "1") (pinfunction "I0_1") (pintype "input"))
    )
    (net (code "150") (name "Net-(IC2A-G1)") (class "Default")
      (node (ref "IC2") (pin "6") (pinfunction "G1_6") (pintype "input"))
      (node (ref "IC3") (pin "6") (pinfunction "G1_6") (pintype "input"))
      (node (ref "R2") (pin "1") (pinfunction "1_1") (pintype "passive"))
    )
    (net (code "151") (name "Net-(IC4A-O)") (class "Default")
      (node (ref "IC4") (pin "3") (pinfunction "O_3") (pintype "output"))
      (node (ref "IC4") (pin "4") (pinfunction "I0_4") (pintype "input"))
    )
    (net (code "152") (name "Net-(IC4B-O)") (class "Default")
      (node (ref "IC4") (pin "6") (pinfunction "O_6") (pintype "output"))
      (node (ref "JP1") (pin "1") (pinfunction "1_1") (pintype "passive"))
    )
    (net (code "153") (name "Net-(IC4C-O)") (class "Default")
      (node (ref "IC4") (pin "8") (pinfunction "O_8") (pintype "output"))
      (node (ref "JP1") (pin "3") (pinfunction "3_3") (pintype "passive"))
    )
    (net (code "154") (name "Net-(IC4D-I0)") (class "Default")
      (node (ref "IC4") (pin "12") (pinfunction "I0_12") (pintype "input"))
      (node (ref "IC6") (pin "11") (pinfunction "O_11") (pintype "output"))
    )
    (net (code "155") (name "Net-(IC4D-O)") (class "Default")
      (node (ref "IC4") (pin "11") (pinfunction "O_11") (pintype "output"))
      (node (ref "JP2") (pin "1") (pinfunction "1_1") (pintype "passive"))
    )
    (net (code "156") (name "Net-(IC5A-O)") (class "Default")
      (node (ref "IC5") (pin "3") (pinfunction "O_3") (pintype "output"))
      (node (ref "IC6") (pin "2") (pinfunction "I1_2") (pintype "input"))
      (node (ref "IC6") (pin "9") (pinfunction "I0_9") (pintype "input"))
    )
    (net (code "157") (name "Net-(IC6A-O)") (class "Default")
      (node (ref "IC6") (pin "3") (pinfunction "O_3") (pintype "output"))
      (node (ref "IC7") (pin "19") (pinfunction "G_19") (pintype "input"))
      (node (ref "IC8") (pin "19") (pinfunction "G_19") (pintype "input"))
    )
    (net (code "158") (name "Net-(IC6B-O)") (class "Default")
      (node (ref "IC6") (pin "6") (pinfunction "O_6") (pintype "output"))
      (node (ref "JP2") (pin "3") (pinfunction "3_3") (pintype "passive"))
    )
    (net (code "159") (name "Net-(IC6C-O)") (class "Default")
      (node (ref "IC6") (pin "8") (pinfunction "O_8") (pintype "output"))
      (node (ref "IC9") (pin "19") (pinfunction "G_19") (pintype "input"))
    )
    (net (code "160") (name "Net-(IC10A-OC)") (class "Default")
      (node (ref "IC10") (pin "1") (pinfunction "OC_1") (pintype "input"))
      (node (ref "IC32") (pin "3") (pinfunction "O_3") (pintype "output"))
    )
    (net (code "161") (name "Net-(IC11A-G)") (class "Default")
      (node (ref "IC11") (pin "1") (pinfunction "G_1") (pintype "input"))
      (node (ref "IC11") (pin "19") (pinfunction "G_19") (pintype "input"))
      (node (ref "IC12") (pin "1") (pinfunction "G_1") (pintype "input"))
      (node (ref "IC12") (pin "19") (pinfunction "G_19") (pintype "input"))
      (node (ref "IC33") (pin "1") (pinfunction "G_1") (pintype "input"))
      (node (ref "IC33") (pin "19") (pinfunction "G_19") (pintype "input"))
      (node (ref "IC34") (pin "1") (pinfunction "G_1") (pintype "input"))
      (node (ref "IC34") (pin "19") (pinfunction "G_19") (pintype "input"))
      (node (ref "J1") (pin "1") (pinfunction "1_1") (pintype "passive"))
      (node (ref "R1") (pin "1") (pinfunction "1_1") (pintype "passive"))
    )
    (net (code "162") (name "Net-(IC13A-O)") (class "Default")
      (node (ref "IC13") (pin "3") (pinfunction "O_3") (pintype "output"))
      (node (ref "IC15") (pin "1") (pinfunction "OC_1") (pintype "input"))
    )
    (net (code "163") (name "Net-(IC13B-O)") (class "Default")
      (node (ref "IC13") (pin "6") (pinfunction "O_6") (pintype "output"))
      (node (ref "IC16") (pin "1") (pinfunction "OC_1") (pintype "input"))
    )
    (net (code "164") (name "Net-(IC13C-O)") (class "Default")
      (node (ref "IC13") (pin "8") (pinfunction "O_8") (pintype "output"))
      (node (ref "IC17") (pin "1") (pinfunction "OC_1") (pintype "input"))
    )
    (net (code "165") (name "Net-(IC13D-O)") (class "Default")
      (node (ref "IC13") (pin "11") (pinfunction "O_11") (pintype "output"))
      (node (ref "IC18") (pin "1") (pinfunction "OC_1") (pintype "input"))
    )
    (net (code "166") (name "Net-(IC19A-O)") (class "Default")
      (node (ref "IC19") (pin "3") (pinfunction "O_3") (pintype "output"))
      (node (ref "IC21") (pin "1") (pinfunction "OC_1") (pintype "input"))
    )
    (net (code "167") (name "Net-(IC19B-O)") (class "Default")
      (node (ref "IC19") (pin "6") (pinfunction "O_6") (pintype "output"))
      (node (ref "IC22") (pin "1") (pinfunction "OC_1") (pintype "input"))
    )
    (net (code "168") (name "Net-(IC19C-O)") (class "Default")
      (node (ref "IC19") (pin "8") (pinfunction "O_8") (pintype "output"))
      (node (ref "IC23") (pin "1") (pinfunction "OC_1") (pintype "input"))
    )
    (net (code "169") (name "Net-(IC19D-O)") (class "Default")
      (node (ref "IC19") (pin "11") (pinfunction "O_11") (pintype "output"))
      (node (ref "IC24") (pin "1") (pinfunction "OC_1") (pintype "input"))
    )
    (net (code "170") (name "Net-(IC25A-OC)") (class "Default")
      (node (ref "IC25") (pin "1") (pinfunction "OC_1") (pintype "input"))
      (node (ref "IC32") (pin "6") (pinfunction "O_6") (pintype "output"))
    )
    (net (code "171") (name "Net-(IC26A-OC)") (class "Default")
      (node (ref "IC26") (pin "1") (pinfunction "OC_1") (pintype "input"))
      (node (ref "IC37") (pin "3") (pinfunction "O_3") (pintype "output"))
    )
    (net (code "172") (name "Net-(IC27A-OC)") (class "Default")
      (node (ref "IC27") (pin "1") (pinfunction "OC_1") (pintype "input"))
      (node (ref "IC37") (pin "6") (pinfunction "O_6") (pintype "output"))
    )
    (net (code "173") (name "Net-(IC28A-OC)") (class "Default")
      (node (ref "IC28") (pin "1") (pinfunction "OC_1") (pintype "input"))
      (node (ref "IC32") (pin "8") (pinfunction "O_8") (pintype "output"))
    )
    (net (code "174") (name "Net-(IC29A-OC)") (class "Default")
      (node (ref "IC29") (pin "1") (pinfunction "OC_1") (pintype "input"))
      (node (ref "IC32") (pin "11") (pinfunction "O_11") (pintype "output"))
    )
    (net (code "175") (name "Net-(IC30A-OC)") (class "Default")
      (node (ref "IC30") (pin "1") (pinfunction "OC_1") (pintype "input"))
      (node (ref "IC37") (pin "8") (pinfunction "O_8") (pintype "output"))
    )
    (net (code "176") (name "Net-(IC31A-OC)") (class "Default")
      (node (ref "IC31") (pin "1") (pinfunction "OC_1") (pintype "input"))
      (node (ref "IC37") (pin "11") (pinfunction "O_11") (pintype "output"))
    )
    (net (code "177") (name "Net-(PWR1-PadA)") (class "Default")
      (node (ref "PWR1") (pin "A") (pinfunction "A_A") (pintype "passive"))
      (node (ref "R4") (pin "1") (pinfunction "1_1") (pintype "passive"))
    )
    (net (code "178") (name "OUT") (class "Default")
      (node (ref "X3") (pin "C27") (pinfunction "B_C27") (pintype "passive"))
    )
    (net (code "179") (name "REG-BRD-LD-ID") (class "Default")
      (node (ref "IC6") (pin "12") (pinfunction "I0_12") (pintype "input"))
      (node (ref "IC6") (pin "13") (pinfunction "I1_13") (pintype "input"))
      (node (ref "IC6") (pin "5") (pinfunction "I1_5") (pintype "input"))
      (node (ref "X3") (pin "B16") (pinfunction "B_B16") (pintype "passive"))
    )
    (net (code "180") (name "REG-BRD-RD-ID") (class "Default")
      (node (ref "IC4") (pin "1") (pinfunction "I0_1") (pintype "input"))
      (node (ref "IC4") (pin "10") (pinfunction "I1_10") (pintype "input"))
      (node (ref "IC4") (pin "2") (pinfunction "I1_2") (pintype "input"))
      (node (ref "X3") (pin "B12") (pinfunction "B_B12") (pintype "passive"))
    )
    (net (code "181") (name "REG-FUNC-LD") (class "Default")
      (node (ref "IC4") (pin "13") (pinfunction "I1_13") (pintype "input"))
      (node (ref "IC6") (pin "4") (pinfunction "I0_4") (pintype "input"))
      (node (ref "X3") (pin "B7") (pinfunction "B_B7") (pintype "passive"))
    )
    (net (code "182") (name "REG-FUNC-RD") (class "Default")
      (node (ref "IC4") (pin "5") (pinfunction "I1_5") (pintype "input"))
      (node (ref "IC4") (pin "9") (pinfunction "I0_9") (pintype "input"))
      (node (ref "X3") (pin "B8") (pinfunction "B_B8") (pintype "passive"))
    )
    (net (code "183") (name "REG-LD-HI") (class "Default")
      (node (ref "IC1") (pin "9") (pinfunction "I_9") (pintype "input"))
      (node (ref "X3") (pin "B23") (pinfunction "B_B23") (pintype "passive"))
    )
    (net (code "184") (name "REG-LD-ID0") (class "Default")
      (node (ref "IC3") (pin "1") (pinfunction "A_1") (pintype "input"))
      (node (ref "X3") (pin "B17") (pinfunction "B_B17") (pintype "passive"))
    )
    (net (code "185") (name "REG-LD-ID1") (class "Default")
      (node (ref "IC3") (pin "2") (pinfunction "B_2") (pintype "input"))
      (node (ref "X3") (pin "B18") (pinfunction "B_B18") (pintype "passive"))
    )
    (net (code "186") (name "REG-LD-ID2") (class "Default")
      (node (ref "IC3") (pin "3") (pinfunction "C_3") (pintype "input"))
      (node (ref "X3") (pin "B19") (pinfunction "B_B19") (pintype "passive"))
    )
    (net (code "187") (name "REG-LD-LO") (class "Default")
      (node (ref "IC1") (pin "3") (pinfunction "I_3") (pintype "input"))
      (node (ref "X3") (pin "B21") (pinfunction "B_B21") (pintype "passive"))
    )
    (net (code "188") (name "REG-RD-HI") (class "Default")
      (node (ref "IC1") (pin "5") (pinfunction "I_5") (pintype "input"))
      (node (ref "X3") (pin "B22") (pinfunction "B_B22") (pintype "passive"))
    )
    (net (code "189") (name "REG-RD-ID0") (class "Default")
      (node (ref "IC2") (pin "1") (pinfunction "A_1") (pintype "input"))
      (node (ref "X3") (pin "B13") (pinfunction "B_B13") (pintype "passive"))
    )
    (net (code "190") (name "REG-RD-ID1") (class "Default")
      (node (ref "IC2") (pin "2") (pinfunction "B_2") (pintype "input"))
      (node (ref "X3") (pin "B14") (pinfunction "B_B14") (pintype "passive"))
    )
    (net (code "191") (name "REG-RD-ID2") (class "Default")
      (node (ref "IC2") (pin "3") (pinfunction "C_3") (pintype "input"))
      (node (ref "X3") (pin "B15") (pinfunction "B_B15") (pintype "passive"))
    )
    (net (code "192") (name "REG-RD-LO") (class "Default")
      (node (ref "IC1") (pin "1") (pinfunction "I_1") (pintype "input"))
      (node (ref "X3") (pin "B20") (pinfunction "B_B20") (pintype "passive"))
    )
    (net (code "193") (name "RESET") (class "Default")
      (node (ref "X3") (pin "C30") (pinfunction "B_C30") (pintype "passive"))
    )
    (net (code "194") (name "RUN") (class "Default")
      (node (ref "X3") (pin "C29") (pinfunction "B_C29") (pintype "passive"))
    )
    (net (code "195") (name "SR-LD") (class "Default")
      (node (ref "X3") (pin "C23") (pinfunction "B_C23") (pintype "passive"))
    )
    (net (code "196") (name "TMP-REG-LD") (class "Default")
      (node (ref "X3") (pin "C3") (pinfunction "B_C3") (pintype "passive"))
    )
    (net (code "197") (name "TMP-REG-RD") (class "Default")
      (node (ref "X3") (pin "C4") (pinfunction "B_C4") (pintype "passive"))
    )
    (net (code "198") (name "UNUSED1") (class "Default")
      (node (ref "X3") (pin "C28") (pinfunction "B_C28") (pintype "passive"))
    )
    (net (code "199") (name "UNUSED2") (class "Default")
      (node (ref "X3") (pin "C6") (pinfunction "B_C6") (pintype "passive"))
    )
    (net (code "200") (name "UNUSED3") (class "Default")
      (node (ref "X3") (pin "C5") (pinfunction "B_C5") (pintype "passive"))
    )
    (net (code "201") (name "UNUSED4") (class "Default")
      (node (ref "X3") (pin "B11") (pinfunction "B_B11") (pintype "passive"))
    )
    (net (code "202") (name "VCC") (class "Default")
      (node (ref "C1") (pin "1") (pinfunction "1_1") (pintype "passive"))
      (node (ref "C10") (pin "1") (pinfunction "1_1") (pintype "passive"))
      (node (ref "C11") (pin "1") (pinfunction "1_1") (pintype "passive"))
      (node (ref "C12") (pin "1") (pinfunction "1_1") (pintype "passive"))
      (node (ref "C13") (pin "1") (pinfunction "1_1") (pintype "passive"))
      (node (ref "C14") (pin "1") (pinfunction "1_1") (pintype "passive"))
      (node (ref "C15") (pin "1") (pinfunction "1_1") (pintype "passive"))
      (node (ref "C16") (pin "1") (pinfunction "1_1") (pintype "passive"))
      (node (ref "C17") (pin "1") (pinfunction "1_1") (pintype "passive"))
      (node (ref "C18") (pin "1") (pinfunction "1_1") (pintype "passive"))
      (node (ref "C19") (pin "1") (pinfunction "1_1") (pintype "passive"))
      (node (ref "C2") (pin "1") (pinfunction "1_1") (pintype "passive"))
      (node (ref "C20") (pin "1") (pinfunction "1_1") (pintype "passive"))
      (node (ref "C21") (pin "1") (pinfunction "1_1") (pintype "passive"))
      (node (ref "C22") (pin "1") (pinfunction "1_1") (pintype "passive"))
      (node (ref "C23") (pin "1") (pinfunction "1_1") (pintype "passive"))
      (node (ref "C24") (pin "1") (pinfunction "1_1") (pintype "passive"))
      (node (ref "C25") (pin "1") (pinfunction "1_1") (pintype "passive"))
      (node (ref "C26") (pin "1") (pinfunction "1_1") (pintype "passive"))
      (node (ref "C27") (pin "1") (pinfunction "1_1") (pintype "passive"))
      (node (ref "C28") (pin "1") (pinfunction "1_1") (pintype "passive"))
      (node (ref "C29") (pin "1") (pinfunction "1_1") (pintype "passive"))
      (node (ref "C3") (pin "1") (pinfunction "1_1") (pintype "passive"))
      (node (ref "C30") (pin "1") (pinfunction "1_1") (pintype "passive"))
      (node (ref "C31") (pin "1") (pinfunction "1_1") (pintype "passive"))
      (node (ref "C32") (pin "1") (pinfunction "1_1") (pintype "passive"))
      (node (ref "C33") (pin "1") (pinfunction "1_1") (pintype "passive"))
      (node (ref "C34") (pin "1") (pinfunction "1_1") (pintype "passive"))
      (node (ref "C35") (pin "1") (pinfunction "1_1") (pintype "passive"))
      (node (ref "C36") (pin "1") (pinfunction "1_1") (pintype "passive"))
      (node (ref "C37") (pin "1") (pinfunction "1_1") (pintype "passive"))
      (node (ref "C4") (pin "1") (pinfunction "1_1") (pintype "passive"))
      (node (ref "C5") (pin "1") (pinfunction "1_1") (pintype "passive"))
      (node (ref "C6") (pin "1") (pinfunction "1_1") (pintype "passive"))
      (node (ref "C7") (pin "1") (pinfunction "1_1") (pintype "passive"))
      (node (ref "C8") (pin "1") (pinfunction "1_1") (pintype "passive"))
      (node (ref "C9") (pin "1") (pinfunction "1_1") (pintype "passive"))
      (node (ref "JP6") (pin "1") (pinfunction "1_1") (pintype "passive"))
      (node (ref "JP6") (pin "2") (pinfunction "2_2") (pintype "passive"))
      (node (ref "R1") (pin "2") (pinfunction "2_2") (pintype "passive"))
      (node (ref "R2") (pin "2") (pinfunction "2_2") (pintype "passive"))
      (node (ref "R4") (pin "2") (pinfunction "2_2") (pintype "passive"))
      (node (ref "RN1") (pin "1") (pinfunction "1_1") (pintype "passive"))
      (node (ref "RN2") (pin "1") (pinfunction "1_1") (pintype "passive"))
      (node (ref "X3") (pin "A2") (pinfunction "B_A2") (pintype "passive"))
      (node (ref "X3") (pin "A31") (pinfunction "B_A31") (pintype "passive"))
      (node (ref "X3") (pin "B2") (pinfunction "B_B2") (pintype "passive"))
      (node (ref "X3") (pin "B31") (pinfunction "B_B31") (pintype "passive"))
      (node (ref "X3") (pin "C2") (pinfunction "B_C2") (pintype "passive"))
      (node (ref "X3") (pin "C31") (pinfunction "B_C31") (pintype "passive"))
    )
    (net (code "203") (name "unconnected-(IC5B-O-Pad6)") (class "Default")
      (node (ref "IC5") (pin "6") (pinfunction "O_6") (pintype "output"))
    )
    (net (code "204") (name "unconnected-(IC5C-O-Pad8)") (class "Default")
      (node (ref "IC5") (pin "8") (pinfunction "O_8") (pintype "output"))
    )
    (net (code "205") (name "unconnected-(IC5D-O-Pad11)") (class "Default")
      (node (ref "IC5") (pin "11") (pinfunction "O_11") (pintype "output"))
    )
    (net (code "206") (name "unconnected-(JP6-Pad35)") (class "Default")
      (node (ref "JP6") (pin "35") (pinfunction "35_35") (pintype "passive"))
    )
    (net (code "207") (name "unconnected-(JP6-Pad36)") (class "Default")
      (node (ref "JP6") (pin "36") (pinfunction "36_36") (pintype "passive"))
    )
    (net (code "208") (name "unconnected-(JP6-Pad37)") (class "Default")
      (node (ref "JP6") (pin "37") (pinfunction "37_37") (pintype "passive"))
    )
    (net (code "209") (name "unconnected-(JP6-Pad38)") (class "Default")
      (node (ref "JP6") (pin "38") (pinfunction "38_38") (pintype "passive"))
    )
  )
)
